# lines_master.net
KiCad netlist of a schematic drawn in EAGLE
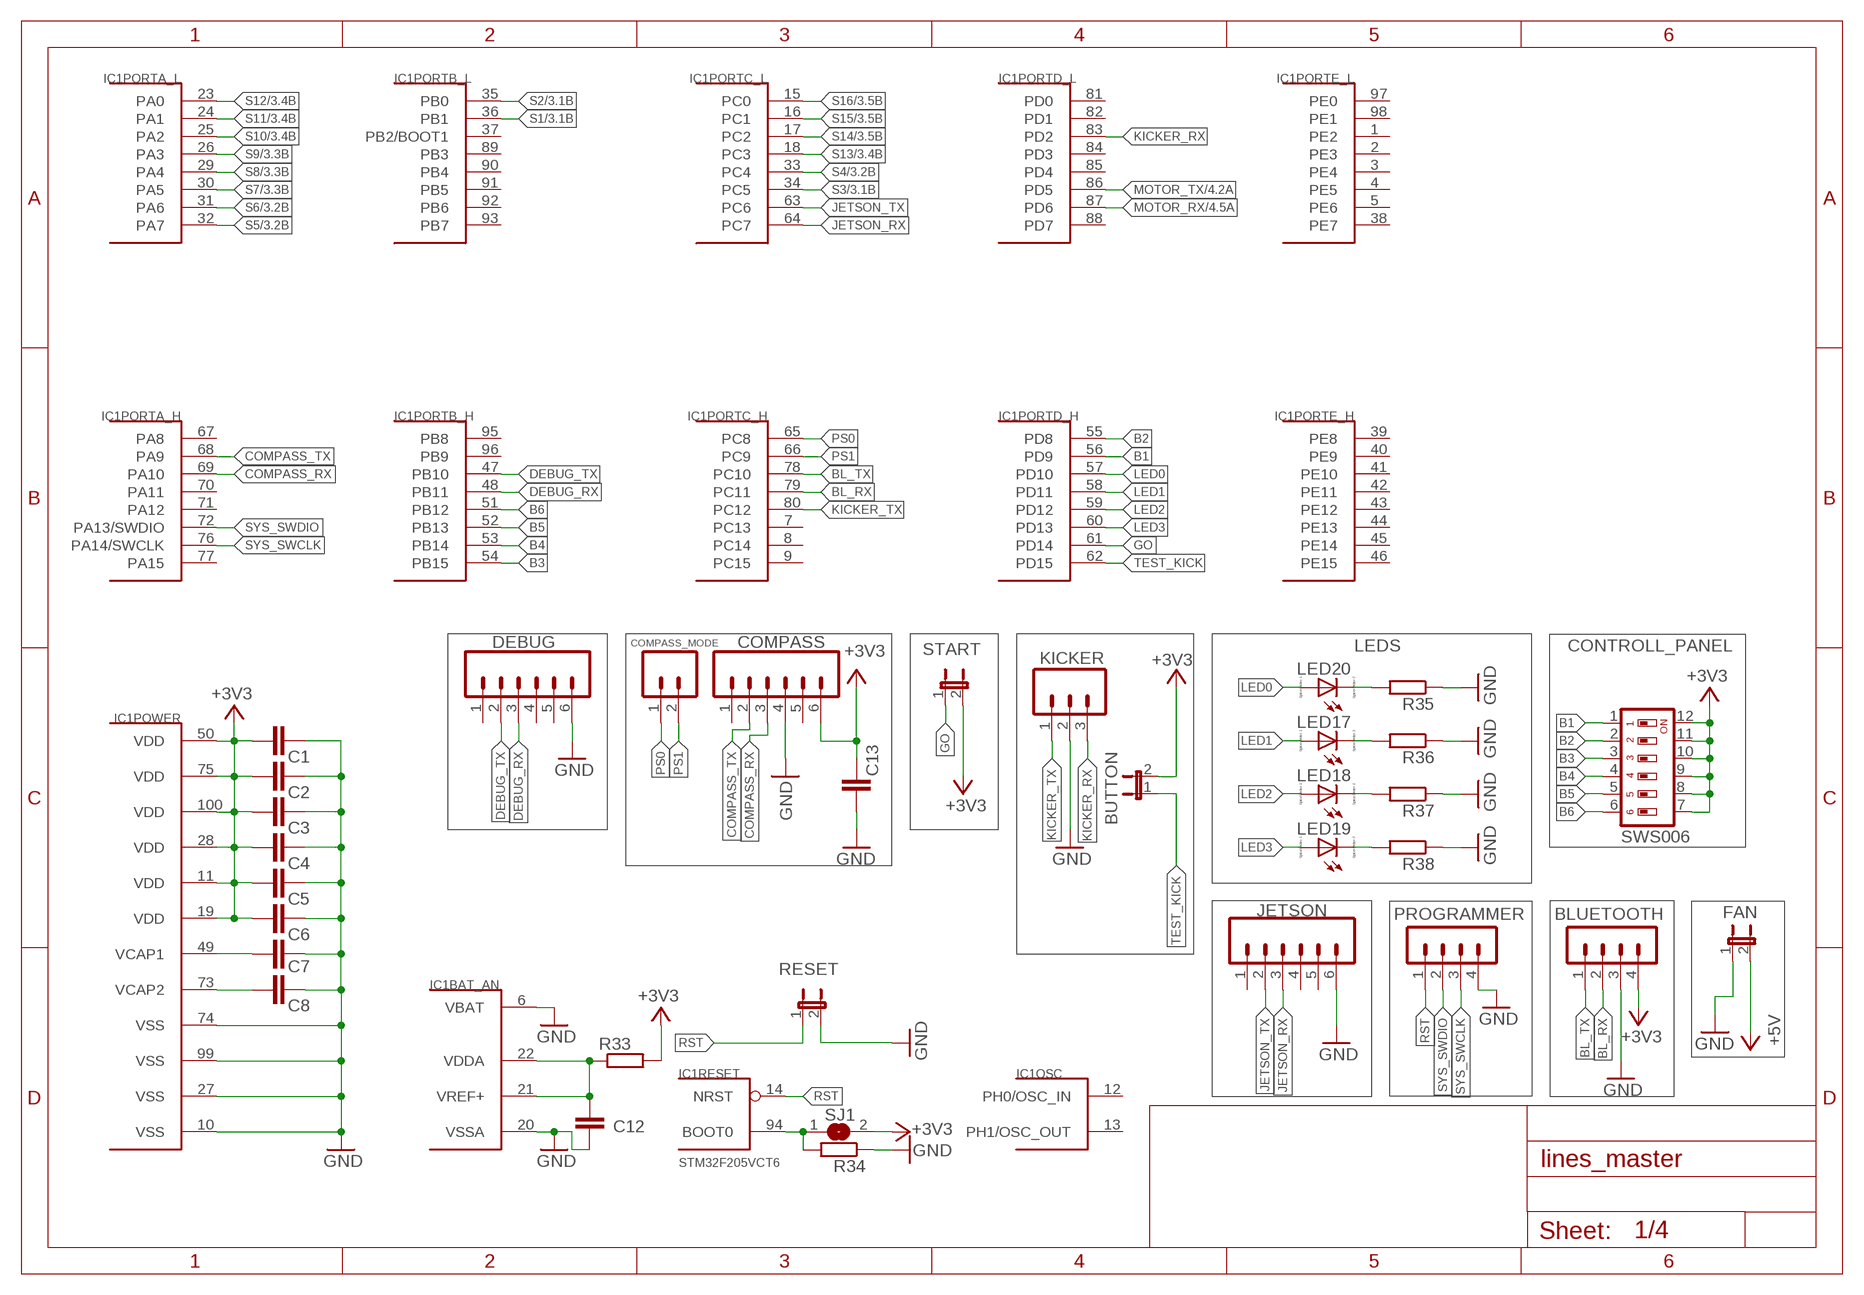
[diagram p0: schematic, sheet 1]
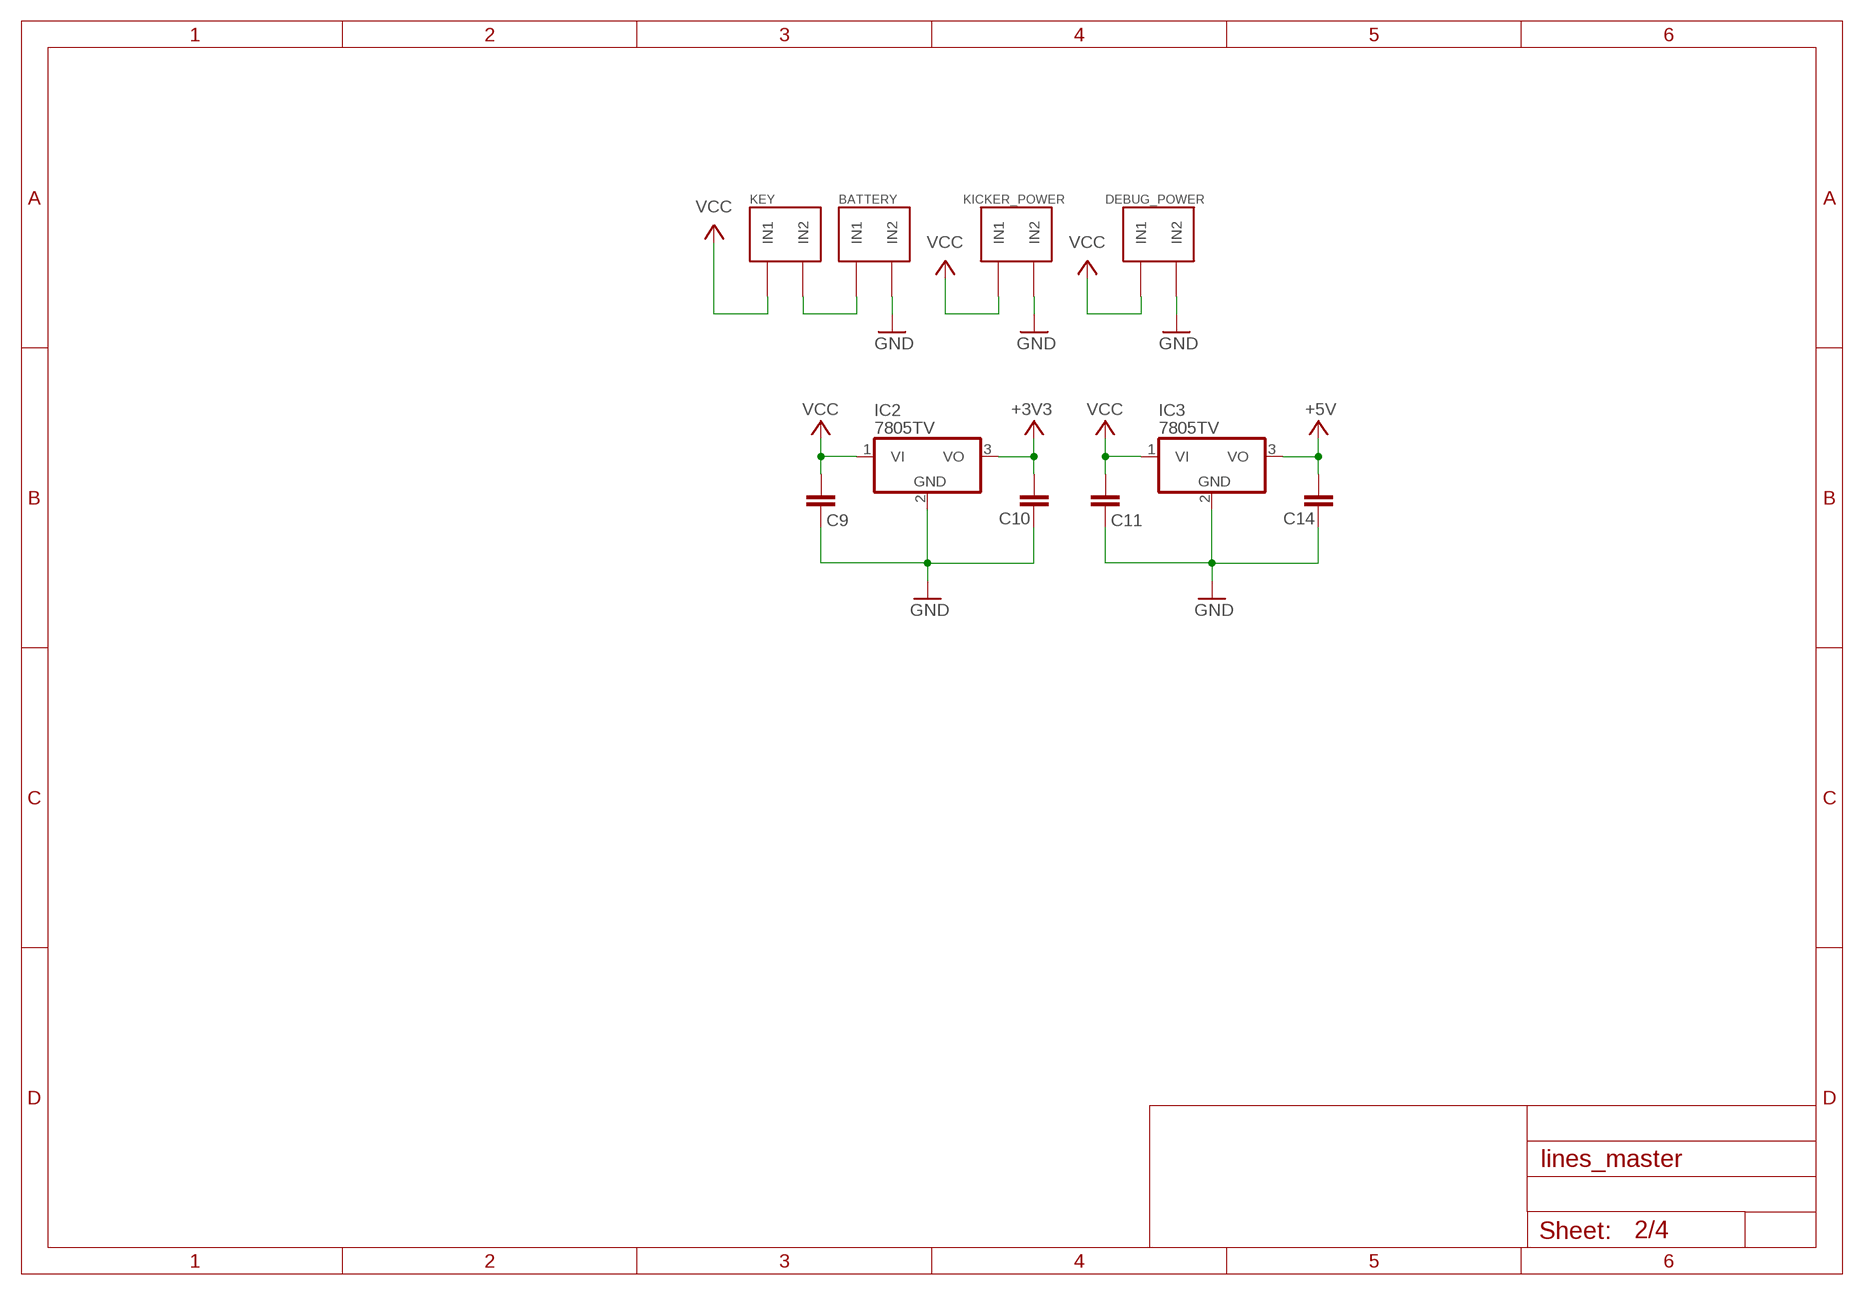
[diagram p1: schematic, sheet 2]
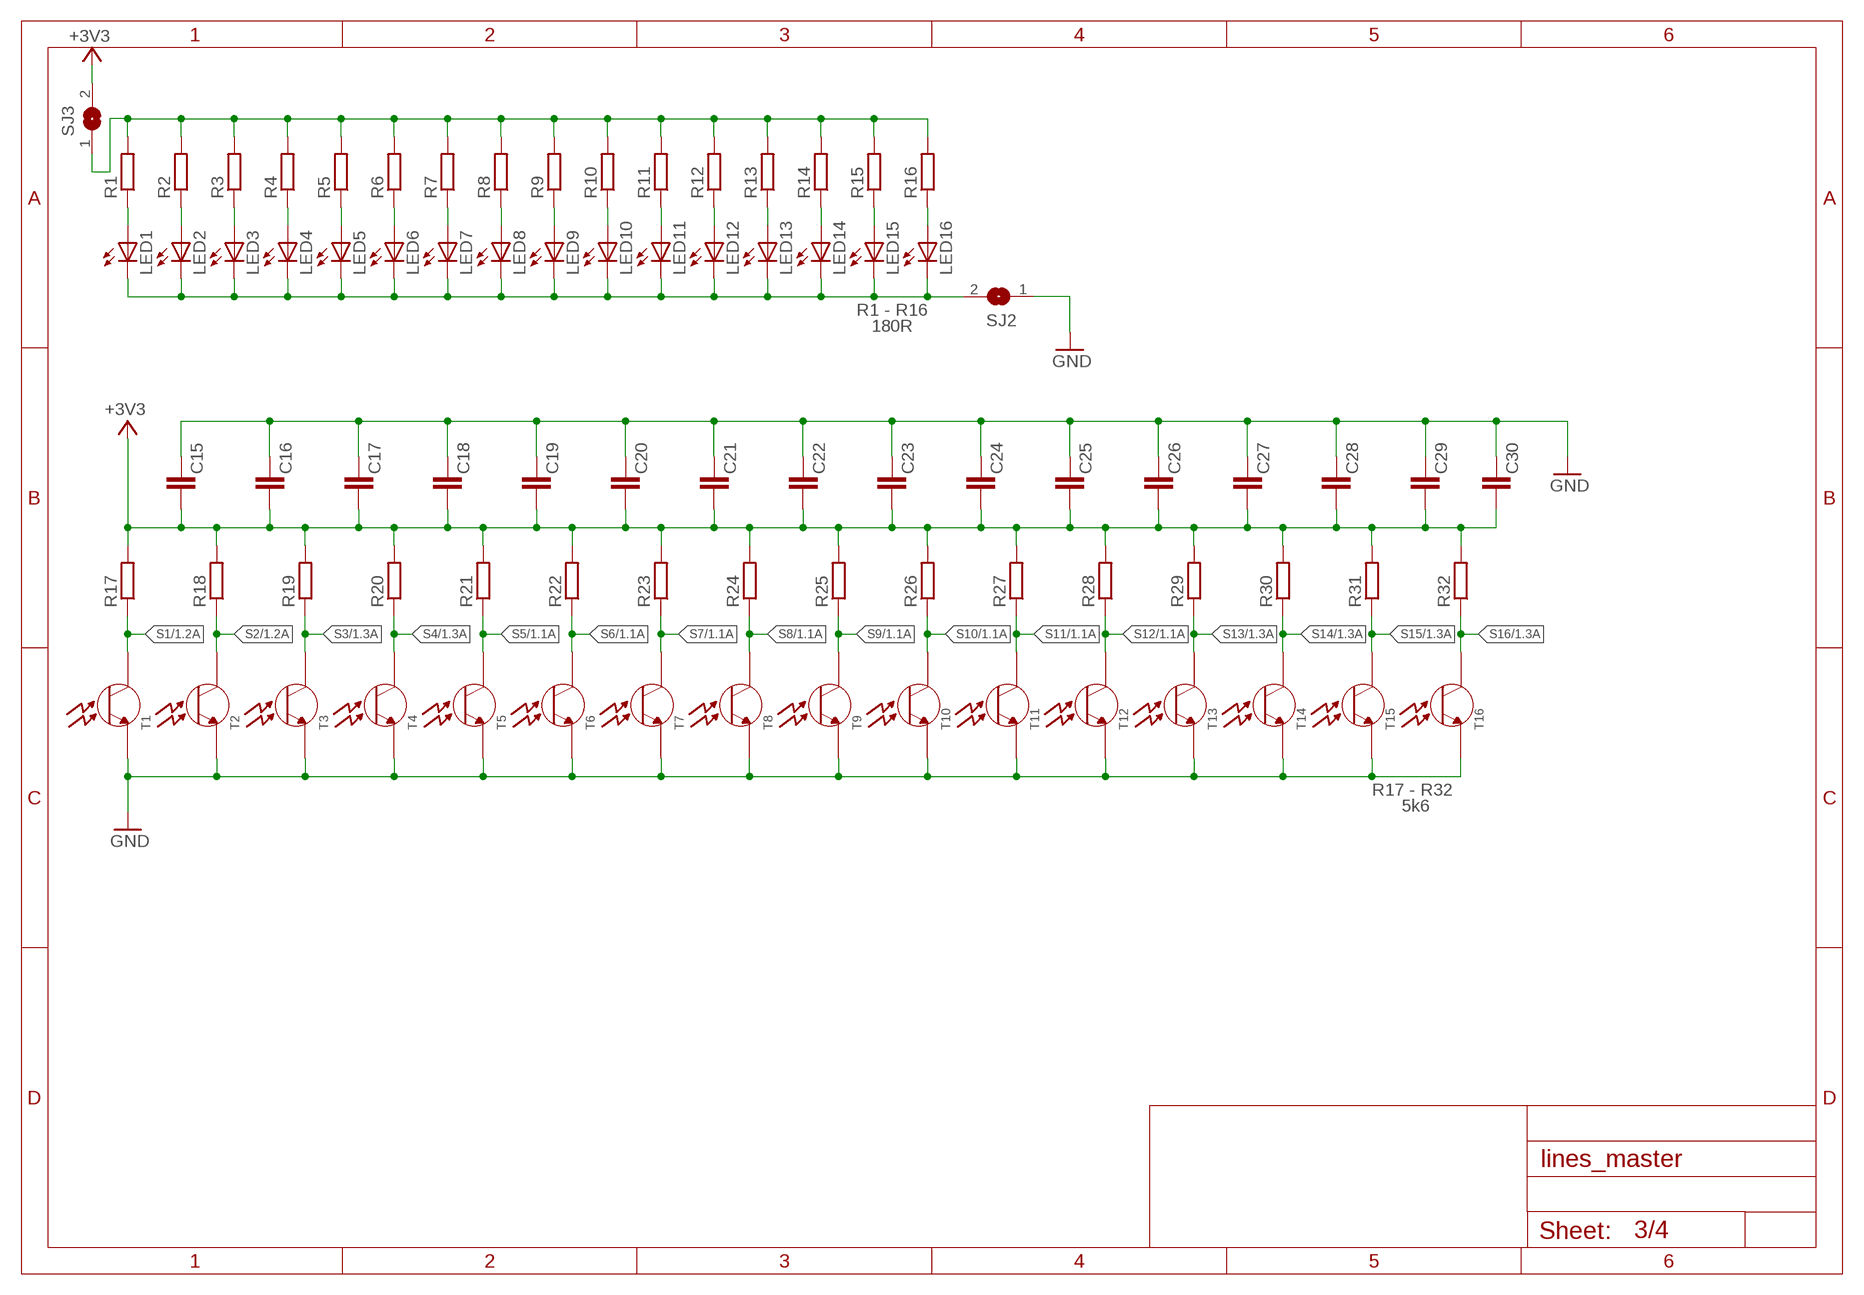
[diagram p2: schematic, sheet 3]
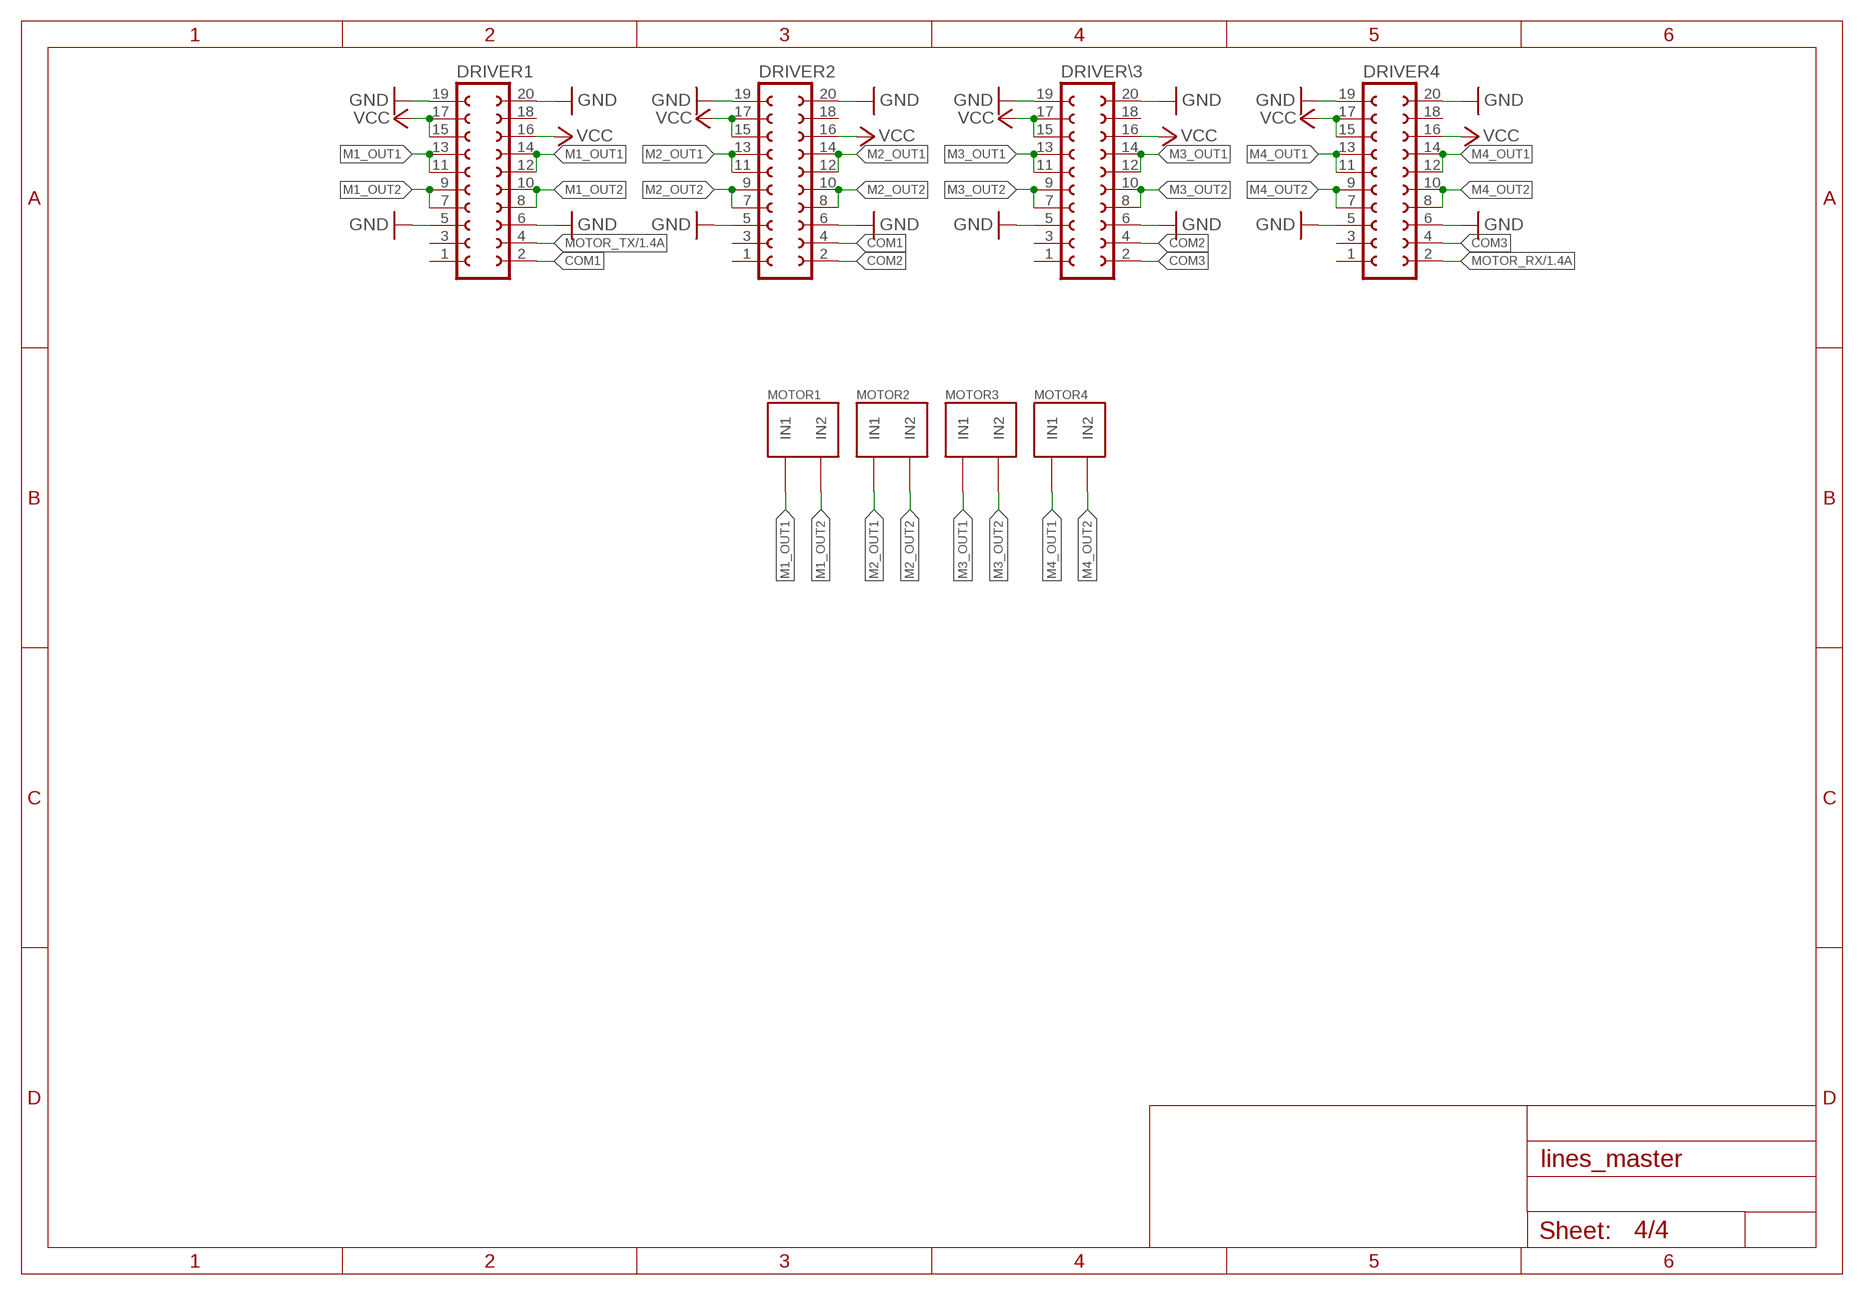
[diagram p3: schematic, sheet 4]

(export (version "E")
  (design (tool "Eeschema 10.0.6"))
  (components
    (comp (ref "DRIVER1")
      (value "FE10-2")
      (footprint "eagle-import:FE10-2")
      (libsource (lib "eagle-import") (part "FE10-2"))
    )
    (comp (ref "DRIVER2")
      (value "FE10-2")
      (footprint "eagle-import:FE10-2")
      (libsource (lib "eagle-import") (part "FE10-2"))
    )
    (comp (ref "DRIVER4")
      (value "FE10-2")
      (footprint "eagle-import:FE10-2")
      (libsource (lib "eagle-import") (part "FE10-2"))
    )
    (comp (ref "DRIVER\\3")
      (value "FE10-2")
      (footprint "eagle-import:FE10-2")
      (libsource (lib "eagle-import") (part "FE10-2"))
    )
    (comp (ref "MOTOR1")
      (value "MOTOR_CONNECTOR")
      (footprint "eagle-import:MOTOR_CONNECTOR")
      (libsource (lib "eagle-import") (part "MOTOR_CONNECTOR"))
    )
    (comp (ref "MOTOR2")
      (value "MOTOR_CONNECTOR")
      (footprint "eagle-import:MOTOR_CONNECTOR")
      (libsource (lib "eagle-import") (part "MOTOR_CONNECTOR"))
    )
    (comp (ref "MOTOR3")
      (value "MOTOR_CONNECTOR")
      (footprint "eagle-import:MOTOR_CONNECTOR")
      (libsource (lib "eagle-import") (part "MOTOR_CONNECTOR"))
    )
    (comp (ref "MOTOR4")
      (value "MOTOR_CONNECTOR")
      (footprint "eagle-import:MOTOR_CONNECTOR")
      (libsource (lib "eagle-import") (part "MOTOR_CONNECTOR"))
    )
    (comp (ref "BLUETOOTH")
      (value "MA04-1")
      (footprint "eagle-import:MA04-1")
      (libsource (lib "eagle-import") (part "MA04-1"))
    )
    (comp (ref "BUTTON")
      (value "JP1E")
      (footprint "eagle-import:JP1")
      (libsource (lib "eagle-import") (part "JP1E"))
    )
    (comp (ref "C1")
      (value "100K")
      (footprint "eagle-import:C0603")
      (libsource (lib "eagle-import") (part "C-EUC0603"))
    )
    (comp (ref "C2")
      (value "100K")
      (footprint "eagle-import:C0603")
      (libsource (lib "eagle-import") (part "C-EUC0603"))
    )
    (comp (ref "C3")
      (value "100K")
      (footprint "eagle-import:C0603")
      (libsource (lib "eagle-import") (part "C-EUC0603"))
    )
    (comp (ref "C4")
      (value "100K")
      (footprint "eagle-import:C0603")
      (libsource (lib "eagle-import") (part "C-EUC0603"))
    )
    (comp (ref "C5")
      (value "100K")
      (footprint "eagle-import:C0603")
      (libsource (lib "eagle-import") (part "C-EUC0603"))
    )
    (comp (ref "C6")
      (value "100K")
      (footprint "eagle-import:C0603")
      (libsource (lib "eagle-import") (part "C-EUC0603"))
    )
    (comp (ref "C7")
      (value "2M2")
      (footprint "eagle-import:C0805")
      (libsource (lib "eagle-import") (part "C-EUC0805"))
    )
    (comp (ref "C8")
      (value "2M2")
      (footprint "eagle-import:C0805")
      (libsource (lib "eagle-import") (part "C-EUC0805"))
    )
    (comp (ref "C12")
      (value "100K")
      (footprint "eagle-import:C0603")
      (libsource (lib "eagle-import") (part "C-EUC0603"))
    )
    (comp (ref "C13")
      (value "100K")
      (footprint "eagle-import:C0603")
      (libsource (lib "eagle-import") (part "C-EUC0603"))
    )
    (comp (ref "COMPASS")
      (value "M06")
      (footprint "eagle-import:06P")
      (libsource (lib "eagle-import") (part "M06"))
    )
    (comp (ref "COMPASS_MODE")
      (value "M02")
      (footprint "eagle-import:02P")
      (libsource (lib "eagle-import") (part "M02"))
    )
    (comp (ref "CONTROLL_PANEL")
      (value "SWS006")
      (footprint "eagle-import:SMS-006")
      (libsource (lib "eagle-import") (part "SWS006"))
    )
    (comp (ref "DEBUG")
      (value "M06")
      (footprint "eagle-import:06P")
      (libsource (lib "eagle-import") (part "M06"))
    )
    (comp (ref "FAN")
      (value "JP1E")
      (footprint "eagle-import:JP1")
      (libsource (lib "eagle-import") (part "JP1E"))
    )
    (comp (ref "IC1")
      (value "STM32F205VCT6")
      (footprint "eagle-import:TQFP100")
      (libsource (lib "eagle-import") (part "STM32F205VCT6"))
    )
    (comp (ref "JETSON")
      (value "M06")
      (footprint "eagle-import:06P")
      (libsource (lib "eagle-import") (part "M06"))
    )
    (comp (ref "KICKER")
      (value "M03")
      (footprint "eagle-import:03P")
      (libsource (lib "eagle-import") (part "M03"))
    )
    (comp (ref "LED17")
      (value "LED_E")
      (footprint "eagle-import:LED_1206")
      (libsource (lib "eagle-import") (part "LED_E"))
    )
    (comp (ref "LED18")
      (value "LED_E")
      (footprint "eagle-import:LED_1206")
      (libsource (lib "eagle-import") (part "LED_E"))
    )
    (comp (ref "LED19")
      (value "LED_E")
      (footprint "eagle-import:LED_1206")
      (libsource (lib "eagle-import") (part "LED_E"))
    )
    (comp (ref "LED20")
      (value "LED_E")
      (footprint "eagle-import:LED_1206")
      (libsource (lib "eagle-import") (part "LED_E"))
    )
    (comp (ref "PROGRAMMER")
      (value "MA04-1")
      (footprint "eagle-import:MA04-1")
      (libsource (lib "eagle-import") (part "MA04-1"))
    )
    (comp (ref "R33")
      (value "R-EU_R1206")
      (footprint "eagle-import:R1206")
      (libsource (lib "eagle-import") (part "R-EU_R1206"))
    )
    (comp (ref "R34")
      (value "R-EU_R0603")
      (footprint "eagle-import:R0603")
      (libsource (lib "eagle-import") (part "R-EU_R0603"))
    )
    (comp (ref "R35")
      (value "R-EU_R0603")
      (footprint "eagle-import:R0603")
      (libsource (lib "eagle-import") (part "R-EU_R0603"))
    )
    (comp (ref "R36")
      (value "R-EU_R0603")
      (footprint "eagle-import:R0603")
      (libsource (lib "eagle-import") (part "R-EU_R0603"))
    )
    (comp (ref "R37")
      (value "R-EU_R0603")
      (footprint "eagle-import:R0603")
      (libsource (lib "eagle-import") (part "R-EU_R0603"))
    )
    (comp (ref "R38")
      (value "R-EU_R0603")
      (footprint "eagle-import:R0603")
      (libsource (lib "eagle-import") (part "R-EU_R0603"))
    )
    (comp (ref "RESET")
      (value "JP1E")
      (footprint "eagle-import:JP1")
      (libsource (lib "eagle-import") (part "JP1E"))
    )
    (comp (ref "SJ1") (value "SJ") (footprint "eagle-import:SJ") (libsource (lib "eagle-import") (part "SJ")))
    (comp (ref "START")
      (value "JP1E")
      (footprint "eagle-import:JP1")
      (libsource (lib "eagle-import") (part "JP1E"))
    )
    (comp (ref "BATTERY")
      (value "MOTOR_CONNECTOR")
      (footprint "eagle-import:MOTOR_CONNECTOR")
      (libsource (lib "eagle-import") (part "MOTOR_CONNECTOR"))
    )
    (comp (ref "C9")
      (value "100K")
      (footprint "eagle-import:C0603")
      (libsource (lib "eagle-import") (part "C-EUC0603"))
    )
    (comp (ref "C10")
      (value "100K")
      (footprint "eagle-import:C0603")
      (libsource (lib "eagle-import") (part "C-EUC0603"))
    )
    (comp (ref "C11")
      (value "100K")
      (footprint "eagle-import:C0603")
      (libsource (lib "eagle-import") (part "C-EUC0603"))
    )
    (comp (ref "C14")
      (value "100K")
      (footprint "eagle-import:C0603")
      (libsource (lib "eagle-import") (part "C-EUC0603"))
    )
    (comp (ref "DEBUG_POWER")
      (value "MOTOR_CONNECTOR")
      (footprint "eagle-import:MOTOR_CONNECTOR")
      (libsource (lib "eagle-import") (part "MOTOR_CONNECTOR"))
    )
    (comp (ref "IC2")
      (value "7805TV")
      (footprint "eagle-import:TO220V")
      (libsource (lib "eagle-import") (part "78TV05"))
    )
    (comp (ref "IC3")
      (value "7805TV")
      (footprint "eagle-import:TO220V")
      (libsource (lib "eagle-import") (part "78TV05"))
    )
    (comp (ref "KEY")
      (value "MOTOR_CONNECTOR")
      (footprint "eagle-import:MOTOR_CONNECTOR")
      (libsource (lib "eagle-import") (part "MOTOR_CONNECTOR"))
    )
    (comp (ref "KICKER_POWER")
      (value "MOTOR_CONNECTOR")
      (footprint "eagle-import:MOTOR_CONNECTOR")
      (libsource (lib "eagle-import") (part "MOTOR_CONNECTOR"))
    )
    (comp (ref "C15")
      (value "100K")
      (footprint "eagle-import:C0603")
      (libsource (lib "eagle-import") (part "C-EUC0603"))
    )
    (comp (ref "C16")
      (value "100K")
      (footprint "eagle-import:C0603")
      (libsource (lib "eagle-import") (part "C-EUC0603"))
    )
    (comp (ref "C17")
      (value "100K")
      (footprint "eagle-import:C0603")
      (libsource (lib "eagle-import") (part "C-EUC0603"))
    )
    (comp (ref "C18")
      (value "100K")
      (footprint "eagle-import:C0603")
      (libsource (lib "eagle-import") (part "C-EUC0603"))
    )
    (comp (ref "C19")
      (value "100K")
      (footprint "eagle-import:C0603")
      (libsource (lib "eagle-import") (part "C-EUC0603"))
    )
    (comp (ref "C20")
      (value "100K")
      (footprint "eagle-import:C0603")
      (libsource (lib "eagle-import") (part "C-EUC0603"))
    )
    (comp (ref "C21")
      (value "100K")
      (footprint "eagle-import:C0603")
      (libsource (lib "eagle-import") (part "C-EUC0603"))
    )
    (comp (ref "C22")
      (value "100K")
      (footprint "eagle-import:C0603")
      (libsource (lib "eagle-import") (part "C-EUC0603"))
    )
    (comp (ref "C23")
      (value "100K")
      (footprint "eagle-import:C0603")
      (libsource (lib "eagle-import") (part "C-EUC0603"))
    )
    (comp (ref "C24")
      (value "100K")
      (footprint "eagle-import:C0603")
      (libsource (lib "eagle-import") (part "C-EUC0603"))
    )
    (comp (ref "C25")
      (value "100K")
      (footprint "eagle-import:C0603")
      (libsource (lib "eagle-import") (part "C-EUC0603"))
    )
    (comp (ref "C26")
      (value "100K")
      (footprint "eagle-import:C0603")
      (libsource (lib "eagle-import") (part "C-EUC0603"))
    )
    (comp (ref "C27")
      (value "100K")
      (footprint "eagle-import:C0603")
      (libsource (lib "eagle-import") (part "C-EUC0603"))
    )
    (comp (ref "C28")
      (value "100K")
      (footprint "eagle-import:C0603")
      (libsource (lib "eagle-import") (part "C-EUC0603"))
    )
    (comp (ref "C29")
      (value "100K")
      (footprint "eagle-import:C0603")
      (libsource (lib "eagle-import") (part "C-EUC0603"))
    )
    (comp (ref "C30")
      (value "100K")
      (footprint "eagle-import:C0603")
      (libsource (lib "eagle-import") (part "C-EUC0603"))
    )
    (comp (ref "LED1")
      (value "LEDKA-3528ASYC")
      (footprint "eagle-import:KA-3528ASYC")
      (libsource (lib "eagle-import") (part "LEDKA-3528ASYC"))
    )
    (comp (ref "LED2")
      (value "LEDKA-3528ASYC")
      (footprint "eagle-import:KA-3528ASYC")
      (libsource (lib "eagle-import") (part "LEDKA-3528ASYC"))
    )
    (comp (ref "LED3")
      (value "LEDKA-3528ASYC")
      (footprint "eagle-import:KA-3528ASYC")
      (libsource (lib "eagle-import") (part "LEDKA-3528ASYC"))
    )
    (comp (ref "LED4")
      (value "LEDKA-3528ASYC")
      (footprint "eagle-import:KA-3528ASYC")
      (libsource (lib "eagle-import") (part "LEDKA-3528ASYC"))
    )
    (comp (ref "LED5")
      (value "LEDKA-3528ASYC")
      (footprint "eagle-import:KA-3528ASYC")
      (libsource (lib "eagle-import") (part "LEDKA-3528ASYC"))
    )
    (comp (ref "LED6")
      (value "LEDKA-3528ASYC")
      (footprint "eagle-import:KA-3528ASYC")
      (libsource (lib "eagle-import") (part "LEDKA-3528ASYC"))
    )
    (comp (ref "LED7")
      (value "LEDKA-3528ASYC")
      (footprint "eagle-import:KA-3528ASYC")
      (libsource (lib "eagle-import") (part "LEDKA-3528ASYC"))
    )
    (comp (ref "LED8")
      (value "LEDKA-3528ASYC")
      (footprint "eagle-import:KA-3528ASYC")
      (libsource (lib "eagle-import") (part "LEDKA-3528ASYC"))
    )
    (comp (ref "LED9")
      (value "LEDKA-3528ASYC")
      (footprint "eagle-import:KA-3528ASYC")
      (libsource (lib "eagle-import") (part "LEDKA-3528ASYC"))
    )
    (comp (ref "LED10")
      (value "LEDKA-3528ASYC")
      (footprint "eagle-import:KA-3528ASYC")
      (libsource (lib "eagle-import") (part "LEDKA-3528ASYC"))
    )
    (comp (ref "LED11")
      (value "LEDKA-3528ASYC")
      (footprint "eagle-import:KA-3528ASYC")
      (libsource (lib "eagle-import") (part "LEDKA-3528ASYC"))
    )
    (comp (ref "LED12")
      (value "LEDKA-3528ASYC")
      (footprint "eagle-import:KA-3528ASYC")
      (libsource (lib "eagle-import") (part "LEDKA-3528ASYC"))
    )
    (comp (ref "LED13")
      (value "LEDKA-3528ASYC")
      (footprint "eagle-import:KA-3528ASYC")
      (libsource (lib "eagle-import") (part "LEDKA-3528ASYC"))
    )
    (comp (ref "LED14")
      (value "LEDKA-3528ASYC")
      (footprint "eagle-import:KA-3528ASYC")
      (libsource (lib "eagle-import") (part "LEDKA-3528ASYC"))
    )
    (comp (ref "LED15")
      (value "LEDKA-3528ASYC")
      (footprint "eagle-import:KA-3528ASYC")
      (libsource (lib "eagle-import") (part "LEDKA-3528ASYC"))
    )
    (comp (ref "LED16")
      (value "LEDKA-3528ASYC")
      (footprint "eagle-import:KA-3528ASYC")
      (libsource (lib "eagle-import") (part "LEDKA-3528ASYC"))
    )
    (comp (ref "R1")
      (value "180R")
      (footprint "eagle-import:R0603")
      (libsource (lib "eagle-import") (part "R-EU_R0603"))
    )
    (comp (ref "R2")
      (value "180R")
      (footprint "eagle-import:R0603")
      (libsource (lib "eagle-import") (part "R-EU_R0603"))
    )
    (comp (ref "R3")
      (value "180R")
      (footprint "eagle-import:R0603")
      (libsource (lib "eagle-import") (part "R-EU_R0603"))
    )
    (comp (ref "R4")
      (value "180R")
      (footprint "eagle-import:R0603")
      (libsource (lib "eagle-import") (part "R-EU_R0603"))
    )
    (comp (ref "R5")
      (value "180R")
      (footprint "eagle-import:R0603")
      (libsource (lib "eagle-import") (part "R-EU_R0603"))
    )
    (comp (ref "R6")
      (value "180R")
      (footprint "eagle-import:R0603")
      (libsource (lib "eagle-import") (part "R-EU_R0603"))
    )
    (comp (ref "R7")
      (value "180R")
      (footprint "eagle-import:R0603")
      (libsource (lib "eagle-import") (part "R-EU_R0603"))
    )
    (comp (ref "R8")
      (value "180R")
      (footprint "eagle-import:R0603")
      (libsource (lib "eagle-import") (part "R-EU_R0603"))
    )
    (comp (ref "R9")
      (value "180R")
      (footprint "eagle-import:R0603")
      (libsource (lib "eagle-import") (part "R-EU_R0603"))
    )
    (comp (ref "R10")
      (value "180R")
      (footprint "eagle-import:R0603")
      (libsource (lib "eagle-import") (part "R-EU_R0603"))
    )
    (comp (ref "R11")
      (value "180R")
      (footprint "eagle-import:R0603")
      (libsource (lib "eagle-import") (part "R-EU_R0603"))
    )
    (comp (ref "R12")
      (value "180R")
      (footprint "eagle-import:R0603")
      (libsource (lib "eagle-import") (part "R-EU_R0603"))
    )
    (comp (ref "R13")
      (value "180R")
      (footprint "eagle-import:R0603")
      (libsource (lib "eagle-import") (part "R-EU_R0603"))
    )
    (comp (ref "R14")
      (value "180R")
      (footprint "eagle-import:R0603")
      (libsource (lib "eagle-import") (part "R-EU_R0603"))
    )
    (comp (ref "R15")
      (value "180R")
      (footprint "eagle-import:R0603")
      (libsource (lib "eagle-import") (part "R-EU_R0603"))
    )
    (comp (ref "R16")
      (value "180R")
      (footprint "eagle-import:R0603")
      (libsource (lib "eagle-import") (part "R-EU_R0603"))
    )
    (comp (ref "R17")
      (value "5K6")
      (footprint "eagle-import:R0603")
      (libsource (lib "eagle-import") (part "R-EU_R0603"))
    )
    (comp (ref "R18")
      (value "5K6")
      (footprint "eagle-import:R0603")
      (libsource (lib "eagle-import") (part "R-EU_R0603"))
    )
    (comp (ref "R19")
      (value "5K6")
      (footprint "eagle-import:R0603")
      (libsource (lib "eagle-import") (part "R-EU_R0603"))
    )
    (comp (ref "R20")
      (value "5K6")
      (footprint "eagle-import:R0603")
      (libsource (lib "eagle-import") (part "R-EU_R0603"))
    )
    (comp (ref "R21")
      (value "5K6")
      (footprint "eagle-import:R0603")
      (libsource (lib "eagle-import") (part "R-EU_R0603"))
    )
    (comp (ref "R22")
      (value "5K6")
      (footprint "eagle-import:R0603")
      (libsource (lib "eagle-import") (part "R-EU_R0603"))
    )
    (comp (ref "R23")
      (value "5K6")
      (footprint "eagle-import:R0603")
      (libsource (lib "eagle-import") (part "R-EU_R0603"))
    )
    (comp (ref "R24")
      (value "5K6")
      (footprint "eagle-import:R0603")
      (libsource (lib "eagle-import") (part "R-EU_R0603"))
    )
    (comp (ref "R25")
      (value "5K6")
      (footprint "eagle-import:R0603")
      (libsource (lib "eagle-import") (part "R-EU_R0603"))
    )
    (comp (ref "R26")
      (value "5K6")
      (footprint "eagle-import:R0603")
      (libsource (lib "eagle-import") (part "R-EU_R0603"))
    )
    (comp (ref "R27")
      (value "5K6")
      (footprint "eagle-import:R0603")
      (libsource (lib "eagle-import") (part "R-EU_R0603"))
    )
    (comp (ref "R28")
      (value "5K6")
      (footprint "eagle-import:R0603")
      (libsource (lib "eagle-import") (part "R-EU_R0603"))
    )
    (comp (ref "R29")
      (value "5K6")
      (footprint "eagle-import:R0603")
      (libsource (lib "eagle-import") (part "R-EU_R0603"))
    )
    (comp (ref "R30")
      (value "5K6")
      (footprint "eagle-import:R0603")
      (libsource (lib "eagle-import") (part "R-EU_R0603"))
    )
    (comp (ref "R31")
      (value "5K6")
      (footprint "eagle-import:R0603")
      (libsource (lib "eagle-import") (part "R-EU_R0603"))
    )
    (comp (ref "R32")
      (value "5K6")
      (footprint "eagle-import:R0603")
      (libsource (lib "eagle-import") (part "R-EU_R0603"))
    )
    (comp (ref "SJ2") (value "SJ") (footprint "eagle-import:SJ") (libsource (lib "eagle-import") (part "SJ")))
    (comp (ref "SJ3") (value "SJ") (footprint "eagle-import:SJ") (libsource (lib "eagle-import") (part "SJ")))
    (comp (ref "T1")
      (value "LL-S150-1A")
      (footprint "eagle-import:LL-S150PTC-1A")
      (libsource (lib "eagle-import") (part "LL-S150-1A"))
    )
    (comp (ref "T2")
      (value "LL-S150-1A")
      (footprint "eagle-import:LL-S150PTC-1A")
      (libsource (lib "eagle-import") (part "LL-S150-1A"))
    )
    (comp (ref "T3")
      (value "LL-S150-1A")
      (footprint "eagle-import:LL-S150PTC-1A")
      (libsource (lib "eagle-import") (part "LL-S150-1A"))
    )
    (comp (ref "T4")
      (value "LL-S150-1A")
      (footprint "eagle-import:LL-S150PTC-1A")
      (libsource (lib "eagle-import") (part "LL-S150-1A"))
    )
    (comp (ref "T5")
      (value "LL-S150-1A")
      (footprint "eagle-import:LL-S150PTC-1A")
      (libsource (lib "eagle-import") (part "LL-S150-1A"))
    )
    (comp (ref "T6")
      (value "LL-S150-1A")
      (footprint "eagle-import:LL-S150PTC-1A")
      (libsource (lib "eagle-import") (part "LL-S150-1A"))
    )
    (comp (ref "T7")
      (value "LL-S150-1A")
      (footprint "eagle-import:LL-S150PTC-1A")
      (libsource (lib "eagle-import") (part "LL-S150-1A"))
    )
    (comp (ref "T8")
      (value "LL-S150-1A")
      (footprint "eagle-import:LL-S150PTC-1A")
      (libsource (lib "eagle-import") (part "LL-S150-1A"))
    )
    (comp (ref "T9")
      (value "LL-S150-1A")
      (footprint "eagle-import:LL-S150PTC-1A")
      (libsource (lib "eagle-import") (part "LL-S150-1A"))
    )
    (comp (ref "T10")
      (value "LL-S150-1A")
      (footprint "eagle-import:LL-S150PTC-1A")
      (libsource (lib "eagle-import") (part "LL-S150-1A"))
    )
    (comp (ref "T11")
      (value "LL-S150-1A")
      (footprint "eagle-import:LL-S150PTC-1A")
      (libsource (lib "eagle-import") (part "LL-S150-1A"))
    )
    (comp (ref "T12")
      (value "LL-S150-1A")
      (footprint "eagle-import:LL-S150PTC-1A")
      (libsource (lib "eagle-import") (part "LL-S150-1A"))
    )
    (comp (ref "T13")
      (value "LL-S150-1A")
      (footprint "eagle-import:LL-S150PTC-1A")
      (libsource (lib "eagle-import") (part "LL-S150-1A"))
    )
    (comp (ref "T14")
      (value "LL-S150-1A")
      (footprint "eagle-import:LL-S150PTC-1A")
      (libsource (lib "eagle-import") (part "LL-S150-1A"))
    )
    (comp (ref "T15")
      (value "LL-S150-1A")
      (footprint "eagle-import:LL-S150PTC-1A")
      (libsource (lib "eagle-import") (part "LL-S150-1A"))
    )
    (comp (ref "T16")
      (value "LL-S150-1A")
      (footprint "eagle-import:LL-S150PTC-1A")
      (libsource (lib "eagle-import") (part "LL-S150-1A"))
    )
  )
  (nets
    (net (code "1") (name "+3V3") (class "Default")
      (node (ref "BLUETOOTH") (pin "4") (pinfunction "4_4") (pintype "passive"))
      (node (ref "BUTTON") (pin "2") (pinfunction "2_2") (pintype "passive"))
      (node (ref "C1") (pin "2") (pinfunction "2_2") (pintype "passive"))
      (node (ref "C10") (pin "2") (pinfunction "2_2") (pintype "passive"))
      (node (ref "C13") (pin "1") (pinfunction "1_1") (pintype "passive"))
      (node (ref "C15") (pin "2") (pinfunction "2_2") (pintype "passive"))
      (node (ref "C16") (pin "2") (pinfunction "2_2") (pintype "passive"))
      (node (ref "C17") (pin "2") (pinfunction "2_2") (pintype "passive"))
      (node (ref "C18") (pin "2") (pinfunction "2_2") (pintype "passive"))
      (node (ref "C19") (pin "2") (pinfunction "2_2") (pintype "passive"))
      (node (ref "C2") (pin "2") (pinfunction "2_2") (pintype "passive"))
      (node (ref "C20") (pin "2") (pinfunction "2_2") (pintype "passive"))
      (node (ref "C21") (pin "2") (pinfunction "2_2") (pintype "passive"))
      (node (ref "C22") (pin "2") (pinfunction "2_2") (pintype "passive"))
      (node (ref "C23") (pin "2") (pinfunction "2_2") (pintype "passive"))
      (node (ref "C24") (pin "2") (pinfunction "2_2") (pintype "passive"))
      (node (ref "C25") (pin "2") (pinfunction "2_2") (pintype "passive"))
      (node (ref "C26") (pin "2") (pinfunction "2_2") (pintype "passive"))
      (node (ref "C27") (pin "2") (pinfunction "2_2") (pintype "passive"))
      (node (ref "C28") (pin "2") (pinfunction "2_2") (pintype "passive"))
      (node (ref "C29") (pin "2") (pinfunction "2_2") (pintype "passive"))
      (node (ref "C3") (pin "2") (pinfunction "2_2") (pintype "passive"))
      (node (ref "C30") (pin "2") (pinfunction "2_2") (pintype "passive"))
      (node (ref "C4") (pin "2") (pinfunction "2_2") (pintype "passive"))
      (node (ref "C5") (pin "2") (pinfunction "2_2") (pintype "passive"))
      (node (ref "C6") (pin "2") (pinfunction "2_2") (pintype "passive"))
      (node (ref "COMPASS") (pin "6") (pinfunction "6_6") (pintype "passive"))
      (node (ref "CONTROLL_PANEL") (pin "10") (pinfunction "10_10") (pintype "passive"))
      (node (ref "CONTROLL_PANEL") (pin "11") (pinfunction "11_11") (pintype "passive"))
      (node (ref "CONTROLL_PANEL") (pin "12") (pinfunction "12_12") (pintype "passive"))
      (node (ref "CONTROLL_PANEL") (pin "7") (pinfunction "7_7") (pintype "passive"))
      (node (ref "CONTROLL_PANEL") (pin "8") (pinfunction "8_8") (pintype "passive"))
      (node (ref "CONTROLL_PANEL") (pin "9") (pinfunction "9_9") (pintype "passive"))
      (node (ref "IC1") (pin "100") (pinfunction "VDD_100") (pintype "power_in"))
      (node (ref "IC1") (pin "11") (pinfunction "VDD_11") (pintype "power_in"))
      (node (ref "IC1") (pin "19") (pinfunction "VDD_19") (pintype "power_in"))
      (node (ref "IC1") (pin "28") (pinfunction "VDD_28") (pintype "power_in"))
      (node (ref "IC1") (pin "50") (pinfunction "VDD_50") (pintype "power_in"))
      (node (ref "IC1") (pin "75") (pinfunction "VDD_75") (pintype "power_in"))
      (node (ref "IC2") (pin "3") (pinfunction "VO_3") (pintype "passive"))
      (node (ref "R17") (pin "2") (pinfunction "2_2") (pintype "passive"))
      (node (ref "R18") (pin "2") (pinfunction "2_2") (pintype "passive"))
      (node (ref "R19") (pin "2") (pinfunction "2_2") (pintype "passive"))
      (node (ref "R20") (pin "2") (pinfunction "2_2") (pintype "passive"))
      (node (ref "R21") (pin "2") (pinfunction "2_2") (pintype "passive"))
      (node (ref "R22") (pin "2") (pinfunction "2_2") (pintype "passive"))
      (node (ref "R23") (pin "2") (pinfunction "2_2") (pintype "passive"))
      (node (ref "R24") (pin "2") (pinfunction "2_2") (pintype "passive"))
      (node (ref "R25") (pin "2") (pinfunction "2_2") (pintype "passive"))
      (node (ref "R26") (pin "2") (pinfunction "2_2") (pintype "passive"))
      (node (ref "R27") (pin "2") (pinfunction "2_2") (pintype "passive"))
      (node (ref "R28") (pin "2") (pinfunction "2_2") (pintype "passive"))
      (node (ref "R29") (pin "2") (pinfunction "2_2") (pintype "passive"))
      (node (ref "R30") (pin "2") (pinfunction "2_2") (pintype "passive"))
      (node (ref "R31") (pin "2") (pinfunction "2_2") (pintype "passive"))
      (node (ref "R32") (pin "2") (pinfunction "2_2") (pintype "passive"))
      (node (ref "R33") (pin "2") (pinfunction "2_2") (pintype "passive"))
      (node (ref "SJ1") (pin "2") (pinfunction "2_2") (pintype "passive"))
      (node (ref "SJ3") (pin "2") (pinfunction "2_2") (pintype "passive"))
      (node (ref "START") (pin "2") (pinfunction "2_2") (pintype "passive"))
    )
    (net (code "2") (name "+5V") (class "Default")
      (node (ref "C14") (pin "2") (pinfunction "2_2") (pintype "passive"))
      (node (ref "FAN") (pin "2") (pinfunction "2_2") (pintype "passive"))
      (node (ref "IC3") (pin "3") (pinfunction "VO_3") (pintype "passive"))
    )
    (net (code "3") (name "B1") (class "Default")
      (node (ref "CONTROLL_PANEL") (pin "1") (pinfunction "1_1") (pintype "passive"))
      (node (ref "IC1") (pin "56") (pinfunction "PD9_56") (pintype "bidirectional"))
    )
    (net (code "4") (name "B2") (class "Default")
      (node (ref "CONTROLL_PANEL") (pin "2") (pinfunction "2_2") (pintype "passive"))
      (node (ref "IC1") (pin "55") (pinfunction "PD8_55") (pintype "bidirectional"))
    )
    (net (code "5") (name "B3") (class "Default")
      (node (ref "CONTROLL_PANEL") (pin "3") (pinfunction "3_3") (pintype "passive"))
      (node (ref "IC1") (pin "54") (pinfunction "PB15_54") (pintype "bidirectional"))
    )
    (net (code "6") (name "B4") (class "Default")
      (node (ref "CONTROLL_PANEL") (pin "4") (pinfunction "4_4") (pintype "passive"))
      (node (ref "IC1") (pin "53") (pinfunction "PB14_53") (pintype "bidirectional"))
    )
    (net (code "7") (name "B5") (class "Default")
      (node (ref "CONTROLL_PANEL") (pin "5") (pinfunction "5_5") (pintype "passive"))
      (node (ref "IC1") (pin "52") (pinfunction "PB13_52") (pintype "bidirectional"))
    )
    (net (code "8") (name "B6") (class "Default")
      (node (ref "CONTROLL_PANEL") (pin "6") (pinfunction "6_6") (pintype "passive"))
      (node (ref "IC1") (pin "51") (pinfunction "PB12_51") (pintype "bidirectional"))
    )
    (net (code "9") (name "BL_RX") (class "Default")
      (node (ref "BLUETOOTH") (pin "2") (pinfunction "2_2") (pintype "passive"))
      (node (ref "IC1") (pin "79") (pinfunction "PC11_79") (pintype "bidirectional"))
    )
    (net (code "10") (name "BL_TX") (class "Default")
      (node (ref "BLUETOOTH") (pin "1") (pinfunction "1_1") (pintype "passive"))
      (node (ref "IC1") (pin "78") (pinfunction "PC10_78") (pintype "bidirectional"))
    )
    (net (code "11") (name "COM1") (class "Default")
      (node (ref "DRIVER1") (pin "2") (pinfunction "2_2") (pintype "passive"))
      (node (ref "DRIVER2") (pin "4") (pinfunction "4_4") (pintype "passive"))
    )
    (net (code "12") (name "COM2") (class "Default")
      (node (ref "DRIVER2") (pin "2") (pinfunction "2_2") (pintype "passive"))
      (node (ref "DRIVER\\3") (pin "4") (pinfunction "4_4") (pintype "passive"))
    )
    (net (code "13") (name "COM3") (class "Default")
      (node (ref "DRIVER4") (pin "4") (pinfunction "4_4") (pintype "passive"))
      (node (ref "DRIVER\\3") (pin "2") (pinfunction "2_2") (pintype "passive"))
    )
    (net (code "14") (name "COMPASS_RX") (class "Default")
      (node (ref "COMPASS") (pin "3") (pinfunction "3_3") (pintype "passive"))
      (node (ref "IC1") (pin "69") (pinfunction "PA10_69") (pintype "bidirectional"))
    )
    (net (code "15") (name "COMPASS_TX") (class "Default")
      (node (ref "COMPASS") (pin "2") (pinfunction "2_2") (pintype "passive"))
      (node (ref "IC1") (pin "68") (pinfunction "PA9_68") (pintype "bidirectional"))
    )
    (net (code "16") (name "DEBUG_RX") (class "Default")
      (node (ref "DEBUG") (pin "3") (pinfunction "3_3") (pintype "passive"))
      (node (ref "IC1") (pin "48") (pinfunction "PB11_48") (pintype "bidirectional"))
    )
    (net (code "17") (name "DEBUG_TX") (class "Default")
      (node (ref "DEBUG") (pin "2") (pinfunction "2_2") (pintype "passive"))
      (node (ref "IC1") (pin "47") (pinfunction "PB10_47") (pintype "bidirectional"))
    )
    (net (code "18") (name "GND") (class "Default")
      (node (ref "BATTERY") (pin "IN2") (pinfunction "IN2_IN2") (pintype "bidirectional"))
      (node (ref "BLUETOOTH") (pin "3") (pinfunction "3_3") (pintype "passive"))
      (node (ref "C1") (pin "1") (pinfunction "1_1") (pintype "passive"))
      (node (ref "C10") (pin "1") (pinfunction "1_1") (pintype "passive"))
      (node (ref "C11") (pin "1") (pinfunction "1_1") (pintype "passive"))
      (node (ref "C12") (pin "2") (pinfunction "2_2") (pintype "passive"))
      (node (ref "C13") (pin "2") (pinfunction "2_2") (pintype "passive"))
      (node (ref "C14") (pin "1") (pinfunction "1_1") (pintype "passive"))
      (node (ref "C15") (pin "1") (pinfunction "1_1") (pintype "passive"))
      (node (ref "C16") (pin "1") (pinfunction "1_1") (pintype "passive"))
      (node (ref "C17") (pin "1") (pinfunction "1_1") (pintype "passive"))
      (node (ref "C18") (pin "1") (pinfunction "1_1") (pintype "passive"))
      (node (ref "C19") (pin "1") (pinfunction "1_1") (pintype "passive"))
      (node (ref "C2") (pin "1") (pinfunction "1_1") (pintype "passive"))
      (node (ref "C20") (pin "1") (pinfunction "1_1") (pintype "passive"))
      (node (ref "C21") (pin "1") (pinfunction "1_1") (pintype "passive"))
      (node (ref "C22") (pin "1") (pinfunction "1_1") (pintype "passive"))
      (node (ref "C23") (pin "1") (pinfunction "1_1") (pintype "passive"))
      (node (ref "C24") (pin "1") (pinfunction "1_1") (pintype "passive"))
      (node (ref "C25") (pin "1") (pinfunction "1_1") (pintype "passive"))
      (node (ref "C26") (pin "1") (pinfunction "1_1") (pintype "passive"))
      (node (ref "C27") (pin "1") (pinfunction "1_1") (pintype "passive"))
      (node (ref "C28") (pin "1") (pinfunction "1_1") (pintype "passive"))
      (node (ref "C29") (pin "1") (pinfunction "1_1") (pintype "passive"))
      (node (ref "C3") (pin "1") (pinfunction "1_1") (pintype "passive"))
      (node (ref "C30") (pin "1") (pinfunction "1_1") (pintype "passive"))
      (node (ref "C4") (pin "1") (pinfunction "1_1") (pintype "passive"))
      (node (ref "C5") (pin "1") (pinfunction "1_1") (pintype "passive"))
      (node (ref "C6") (pin "1") (pinfunction "1_1") (pintype "passive"))
      (node (ref "C7") (pin "1") (pinfunction "1_1") (pintype "passive"))
      (node (ref "C8") (pin "1") (pinfunction "1_1") (pintype "passive"))
      (node (ref "C9") (pin "1") (pinfunction "1_1") (pintype "passive"))
      (node (ref "COMPASS") (pin "4") (pinfunction "4_4") (pintype "passive"))
      (node (ref "DEBUG") (pin "6") (pinfunction "6_6") (pintype "passive"))
      (node (ref "DEBUG_POWER") (pin "IN2") (pinfunction "IN2_IN2") (pintype "bidirectional"))
      (node (ref "DRIVER1") (pin "19") (pinfunction "19_19") (pintype "passive"))
      (node (ref "DRIVER1") (pin "20") (pinfunction "20_20") (pintype "passive"))
      (node (ref "DRIVER1") (pin "5") (pinfunction "5_5") (pintype "passive"))
      (node (ref "DRIVER1") (pin "6") (pinfunction "6_6") (pintype "passive"))
      (node (ref "DRIVER2") (pin "19") (pinfunction "19_19") (pintype "passive"))
      (node (ref "DRIVER2") (pin "20") (pinfunction "20_20") (pintype "passive"))
      (node (ref "DRIVER2") (pin "5") (pinfunction "5_5") (pintype "passive"))
      (node (ref "DRIVER2") (pin "6") (pinfunction "6_6") (pintype "passive"))
      (node (ref "DRIVER4") (pin "19") (pinfunction "19_19") (pintype "passive"))
      (node (ref "DRIVER4") (pin "20") (pinfunction "20_20") (pintype "passive"))
      (node (ref "DRIVER4") (pin "5") (pinfunction "5_5") (pintype "passive"))
      (node (ref "DRIVER4") (pin "6") (pinfunction "6_6") (pintype "passive"))
      (node (ref "DRIVER\\3") (pin "19") (pinfunction "19_19") (pintype "passive"))
      (node (ref "DRIVER\\3") (pin "20") (pinfunction "20_20") (pintype "passive"))
      (node (ref "DRIVER\\3") (pin "5") (pinfunction "5_5") (pintype "passive"))
      (node (ref "DRIVER\\3") (pin "6") (pinfunction "6_6") (pintype "passive"))
      (node (ref "FAN") (pin "1") (pinfunction "1_1") (pintype "passive"))
      (node (ref "IC1") (pin "10") (pinfunction "VSS_10") (pintype "power_in"))
      (node (ref "IC1") (pin "20") (pinfunction "VSSA_20") (pintype "power_in"))
      (node (ref "IC1") (pin "27") (pinfunction "VSS_27") (pintype "power_in"))
      (node (ref "IC1") (pin "6") (pinfunction "VBAT_6") (pintype "power_in"))
      (node (ref "IC1") (pin "74") (pinfunction "VSS_74") (pintype "power_in"))
      (node (ref "IC1") (pin "99") (pinfunction "VSS_99") (pintype "power_in"))
      (node (ref "IC2") (pin "2") (pinfunction "GND_2") (pintype "passive"))
      (node (ref "IC3") (pin "2") (pinfunction "GND_2") (pintype "passive"))
      (node (ref "JETSON") (pin "6") (pinfunction "6_6") (pintype "passive"))
      (node (ref "KICKER") (pin "2") (pinfunction "2_2") (pintype "passive"))
      (node (ref "KICKER_POWER") (pin "IN2") (pinfunction "IN2_IN2") (pintype "bidirectional"))
      (node (ref "PROGRAMMER") (pin "4") (pinfunction "4_4") (pintype "passive"))
      (node (ref "R34") (pin "1") (pinfunction "1_1") (pintype "passive"))
      (node (ref "R35") (pin "1") (pinfunction "1_1") (pintype "passive"))
      (node (ref "R36") (pin "1") (pinfunction "1_1") (pintype "passive"))
      (node (ref "R37") (pin "1") (pinfunction "1_1") (pintype "passive"))
      (node (ref "R38") (pin "1") (pinfunction "1_1") (pintype "passive"))
      (node (ref "RESET") (pin "2") (pinfunction "2_2") (pintype "passive"))
      (node (ref "SJ2") (pin "1") (pinfunction "1_1") (pintype "passive"))
      (node (ref "T1") (pin "E") (pinfunction "E_E") (pintype "bidirectional"))
      (node (ref "T10") (pin "E") (pinfunction "E_E") (pintype "bidirectional"))
      (node (ref "T11") (pin "E") (pinfunction "E_E") (pintype "bidirectional"))
      (node (ref "T12") (pin "E") (pinfunction "E_E") (pintype "bidirectional"))
      (node (ref "T13") (pin "E") (pinfunction "E_E") (pintype "bidirectional"))
      (node (ref "T14") (pin "E") (pinfunction "E_E") (pintype "bidirectional"))
      (node (ref "T15") (pin "E") (pinfunction "E_E") (pintype "bidirectional"))
      (node (ref "T16") (pin "E") (pinfunction "E_E") (pintype "bidirectional"))
      (node (ref "T2") (pin "E") (pinfunction "E_E") (pintype "bidirectional"))
      (node (ref "T3") (pin "E") (pinfunction "E_E") (pintype "bidirectional"))
      (node (ref "T4") (pin "E") (pinfunction "E_E") (pintype "bidirectional"))
      (node (ref "T5") (pin "E") (pinfunction "E_E") (pintype "bidirectional"))
      (node (ref "T6") (pin "E") (pinfunction "E_E") (pintype "bidirectional"))
      (node (ref "T7") (pin "E") (pinfunction "E_E") (pintype "bidirectional"))
      (node (ref "T8") (pin "E") (pinfunction "E_E") (pintype "bidirectional"))
      (node (ref "T9") (pin "E") (pinfunction "E_E") (pintype "bidirectional"))
    )
    (net (code "19") (name "GO") (class "Default")
      (node (ref "IC1") (pin "61") (pinfunction "PD14_61") (pintype "bidirectional"))
      (node (ref "START") (pin "1") (pinfunction "1_1") (pintype "passive"))
    )
    (net (code "20") (name "JETSON_RX") (class "Default")
      (node (ref "IC1") (pin "64") (pinfunction "PC7_64") (pintype "bidirectional"))
      (node (ref "JETSON") (pin "3") (pinfunction "3_3") (pintype "passive"))
    )
    (net (code "21") (name "JETSON_TX") (class "Default")
      (node (ref "IC1") (pin "63") (pinfunction "PC6_63") (pintype "bidirectional"))
      (node (ref "JETSON") (pin "2") (pinfunction "2_2") (pintype "passive"))
    )
    (net (code "22") (name "KICKER_RX") (class "Default")
      (node (ref "IC1") (pin "83") (pinfunction "PD2_83") (pintype "bidirectional"))
      (node (ref "KICKER") (pin "3") (pinfunction "3_3") (pintype "passive"))
    )
    (net (code "23") (name "KICKER_TX") (class "Default")
      (node (ref "IC1") (pin "80") (pinfunction "PC12_80") (pintype "bidirectional"))
      (node (ref "KICKER") (pin "1") (pinfunction "1_1") (pintype "passive"))
    )
    (net (code "24") (name "LED0") (class "Default")
      (node (ref "IC1") (pin "57") (pinfunction "PD10_57") (pintype "bidirectional"))
      (node (ref "LED20") (pin "A") (pinfunction "A_A") (pintype "passive"))
    )
    (net (code "25") (name "LED1") (class "Default")
      (node (ref "IC1") (pin "58") (pinfunction "PD11_58") (pintype "bidirectional"))
      (node (ref "LED17") (pin "A") (pinfunction "A_A") (pintype "passive"))
    )
    (net (code "26") (name "LED2") (class "Default")
      (node (ref "IC1") (pin "59") (pinfunction "PD12_59") (pintype "bidirectional"))
      (node (ref "LED18") (pin "A") (pinfunction "A_A") (pintype "passive"))
    )
    (net (code "27") (name "LED3") (class "Default")
      (node (ref "IC1") (pin "60") (pinfunction "PD13_60") (pintype "bidirectional"))
      (node (ref "LED19") (pin "A") (pinfunction "A_A") (pintype "passive"))
    )
    (net (code "28") (name "M1_OUT1") (class "Default")
      (node (ref "DRIVER1") (pin "11") (pinfunction "11_11") (pintype "passive"))
      (node (ref "DRIVER1") (pin "12") (pinfunction "12_12") (pintype "passive"))
      (node (ref "DRIVER1") (pin "13") (pinfunction "13_13") (pintype "passive"))
      (node (ref "DRIVER1") (pin "14") (pinfunction "14_14") (pintype "passive"))
      (node (ref "MOTOR1") (pin "IN1") (pinfunction "IN1_IN1") (pintype "bidirectional"))
    )
    (net (code "29") (name "M1_OUT2") (class "Default")
      (node (ref "DRIVER1") (pin "10") (pinfunction "10_10") (pintype "passive"))
      (node (ref "DRIVER1") (pin "7") (pinfunction "7_7") (pintype "passive"))
      (node (ref "DRIVER1") (pin "8") (pinfunction "8_8") (pintype "passive"))
      (node (ref "DRIVER1") (pin "9") (pinfunction "9_9") (pintype "passive"))
      (node (ref "MOTOR1") (pin "IN2") (pinfunction "IN2_IN2") (pintype "bidirectional"))
    )
    (net (code "30") (name "M2_OUT1") (class "Default")
      (node (ref "DRIVER2") (pin "11") (pinfunction "11_11") (pintype "passive"))
      (node (ref "DRIVER2") (pin "12") (pinfunction "12_12") (pintype "passive"))
      (node (ref "DRIVER2") (pin "13") (pinfunction "13_13") (pintype "passive"))
      (node (ref "DRIVER2") (pin "14") (pinfunction "14_14") (pintype "passive"))
      (node (ref "MOTOR2") (pin "IN1") (pinfunction "IN1_IN1") (pintype "bidirectional"))
    )
    (net (code "31") (name "M2_OUT2") (class "Default")
      (node (ref "DRIVER2") (pin "10") (pinfunction "10_10") (pintype "passive"))
      (node (ref "DRIVER2") (pin "7") (pinfunction "7_7") (pintype "passive"))
      (node (ref "DRIVER2") (pin "8") (pinfunction "8_8") (pintype "passive"))
      (node (ref "DRIVER2") (pin "9") (pinfunction "9_9") (pintype "passive"))
      (node (ref "MOTOR2") (pin "IN2") (pinfunction "IN2_IN2") (pintype "bidirectional"))
    )
    (net (code "32") (name "M3_OUT1") (class "Default")
      (node (ref "DRIVER\\3") (pin "11") (pinfunction "11_11") (pintype "passive"))
      (node (ref "DRIVER\\3") (pin "12") (pinfunction "12_12") (pintype "passive"))
      (node (ref "DRIVER\\3") (pin "13") (pinfunction "13_13") (pintype "passive"))
      (node (ref "DRIVER\\3") (pin "14") (pinfunction "14_14") (pintype "passive"))
      (node (ref "MOTOR3") (pin "IN1") (pinfunction "IN1_IN1") (pintype "bidirectional"))
    )
    (net (code "33") (name "M3_OUT2") (class "Default")
      (node (ref "DRIVER\\3") (pin "10") (pinfunction "10_10") (pintype "passive"))
      (node (ref "DRIVER\\3") (pin "7") (pinfunction "7_7") (pintype "passive"))
      (node (ref "DRIVER\\3") (pin "8") (pinfunction "8_8") (pintype "passive"))
      (node (ref "DRIVER\\3") (pin "9") (pinfunction "9_9") (pintype "passive"))
      (node (ref "MOTOR3") (pin "IN2") (pinfunction "IN2_IN2") (pintype "bidirectional"))
    )
    (net (code "34") (name "M4_OUT1") (class "Default")
      (node (ref "DRIVER4") (pin "11") (pinfunction "11_11") (pintype "passive"))
      (node (ref "DRIVER4") (pin "12") (pinfunction "12_12") (pintype "passive"))
      (node (ref "DRIVER4") (pin "13") (pinfunction "13_13") (pintype "passive"))
      (node (ref "DRIVER4") (pin "14") (pinfunction "14_14") (pintype "passive"))
      (node (ref "MOTOR4") (pin "IN1") (pinfunction "IN1_IN1") (pintype "bidirectional"))
    )
    (net (code "35") (name "M4_OUT2") (class "Default")
      (node (ref "DRIVER4") (pin "10") (pinfunction "10_10") (pintype "passive"))
      (node (ref "DRIVER4") (pin "7") (pinfunction "7_7") (pintype "passive"))
      (node (ref "DRIVER4") (pin "8") (pinfunction "8_8") (pintype "passive"))
      (node (ref "DRIVER4") (pin "9") (pinfunction "9_9") (pintype "passive"))
      (node (ref "MOTOR4") (pin "IN2") (pinfunction "IN2_IN2") (pintype "bidirectional"))
    )
    (net (code "36") (name "MOTOR_RX") (class "Default")
      (node (ref "DRIVER4") (pin "2") (pinfunction "2_2") (pintype "passive"))
      (node (ref "IC1") (pin "87") (pinfunction "PD6_87") (pintype "bidirectional"))
    )
    (net (code "37") (name "MOTOR_TX") (class "Default")
      (node (ref "DRIVER1") (pin "4") (pinfunction "4_4") (pintype "passive"))
      (node (ref "IC1") (pin "86") (pinfunction "PD5_86") (pintype "bidirectional"))
    )
    (net (code "38") (name "Net-(BATTERY-PadIN1)") (class "Default")
      (node (ref "BATTERY") (pin "IN1") (pinfunction "IN1_IN1") (pintype "bidirectional"))
      (node (ref "KEY") (pin "IN2") (pinfunction "IN2_IN2") (pintype "bidirectional"))
    )
    (net (code "39") (name "Net-(IC1A-VDDA)") (class "Default")
      (node (ref "C12") (pin "1") (pinfunction "1_1") (pintype "passive"))
      (node (ref "IC1") (pin "21") (pinfunction "VREF+_21") (pintype "input"))
      (node (ref "IC1") (pin "22") (pinfunction "VDDA_22") (pintype "power_in"))
      (node (ref "R33") (pin "1") (pinfunction "1_1") (pintype "passive"))
    )
    (net (code "40") (name "Net-(IC1M-VCAP1)") (class "Default")
      (node (ref "C7") (pin "2") (pinfunction "2_2") (pintype "passive"))
      (node (ref "IC1") (pin "49") (pinfunction "VCAP1_49") (pintype "power_in"))
    )
    (net (code "41") (name "Net-(IC1M-VCAP2)") (class "Default")
      (node (ref "C8") (pin "2") (pinfunction "2_2") (pintype "passive"))
      (node (ref "IC1") (pin "73") (pinfunction "VCAP2_73") (pintype "power_in"))
    )
    (net (code "42") (name "Net-(IC1N-BOOT0)") (class "Default")
      (node (ref "IC1") (pin "94") (pinfunction "BOOT0_94") (pintype "input"))
      (node (ref "R34") (pin "2") (pinfunction "2_2") (pintype "passive"))
      (node (ref "SJ1") (pin "1") (pinfunction "1_1") (pintype "passive"))
    )
    (net (code "43") (name "Net-(LED1-PadA)") (class "Default")
      (node (ref "LED1") (pin "A") (pinfunction "A_A") (pintype "passive"))
      (node (ref "R1") (pin "1") (pinfunction "1_1") (pintype "passive"))
    )
    (net (code "44") (name "Net-(LED1-PadC)") (class "Default")
      (node (ref "LED1") (pin "C") (pinfunction "C_C") (pintype "passive"))
      (node (ref "LED10") (pin "C") (pinfunction "C_C") (pintype "passive"))
      (node (ref "LED11") (pin "C") (pinfunction "C_C") (pintype "passive"))
      (node (ref "LED12") (pin "C") (pinfunction "C_C") (pintype "passive"))
      (node (ref "LED13") (pin "C") (pinfunction "C_C") (pintype "passive"))
      (node (ref "LED14") (pin "C") (pinfunction "C_C") (pintype "passive"))
      (node (ref "LED15") (pin "C") (pinfunction "C_C") (pintype "passive"))
      (node (ref "LED16") (pin "C") (pinfunction "C_C") (pintype "passive"))
      (node (ref "LED2") (pin "C") (pinfunction "C_C") (pintype "passive"))
      (node (ref "LED3") (pin "C") (pinfunction "C_C") (pintype "passive"))
      (node (ref "LED4") (pin "C") (pinfunction "C_C") (pintype "passive"))
      (node (ref "LED5") (pin "C") (pinfunction "C_C") (pintype "passive"))
      (node (ref "LED6") (pin "C") (pinfunction "C_C") (pintype "passive"))
      (node (ref "LED7") (pin "C") (pinfunction "C_C") (pintype "passive"))
      (node (ref "LED8") (pin "C") (pinfunction "C_C") (pintype "passive"))
      (node (ref "LED9") (pin "C") (pinfunction "C_C") (pintype "passive"))
      (node (ref "SJ2") (pin "2") (pinfunction "2_2") (pintype "passive"))
    )
    (net (code "45") (name "Net-(LED2-PadA)") (class "Default")
      (node (ref "LED2") (pin "A") (pinfunction "A_A") (pintype "passive"))
      (node (ref "R2") (pin "1") (pinfunction "1_1") (pintype "passive"))
    )
    (net (code "46") (name "Net-(LED3-PadA)") (class "Default")
      (node (ref "LED3") (pin "A") (pinfunction "A_A") (pintype "passive"))
      (node (ref "R3") (pin "1") (pinfunction "1_1") (pintype "passive"))
    )
    (net (code "47") (name "Net-(LED4-PadA)") (class "Default")
      (node (ref "LED4") (pin "A") (pinfunction "A_A") (pintype "passive"))
      (node (ref "R4") (pin "1") (pinfunction "1_1") (pintype "passive"))
    )
    (net (code "48") (name "Net-(LED5-PadA)") (class "Default")
      (node (ref "LED5") (pin "A") (pinfunction "A_A") (pintype "passive"))
      (node (ref "R5") (pin "1") (pinfunction "1_1") (pintype "passive"))
    )
    (net (code "49") (name "Net-(LED6-PadA)") (class "Default")
      (node (ref "LED6") (pin "A") (pinfunction "A_A") (pintype "passive"))
      (node (ref "R6") (pin "1") (pinfunction "1_1") (pintype "passive"))
    )
    (net (code "50") (name "Net-(LED7-PadA)") (class "Default")
      (node (ref "LED7") (pin "A") (pinfunction "A_A") (pintype "passive"))
      (node (ref "R7") (pin "1") (pinfunction "1_1") (pintype "passive"))
    )
    (net (code "51") (name "Net-(LED8-PadA)") (class "Default")
      (node (ref "LED8") (pin "A") (pinfunction "A_A") (pintype "passive"))
      (node (ref "R8") (pin "1") (pinfunction "1_1") (pintype "passive"))
    )
    (net (code "52") (name "Net-(LED9-PadA)") (class "Default")
      (node (ref "LED9") (pin "A") (pinfunction "A_A") (pintype "passive"))
      (node (ref "R9") (pin "1") (pinfunction "1_1") (pintype "passive"))
    )
    (net (code "53") (name "Net-(LED10-PadA)") (class "Default")
      (node (ref "LED10") (pin "A") (pinfunction "A_A") (pintype "passive"))
      (node (ref "R10") (pin "1") (pinfunction "1_1") (pintype "passive"))
    )
    (net (code "54") (name "Net-(LED11-PadA)") (class "Default")
      (node (ref "LED11") (pin "A") (pinfunction "A_A") (pintype "passive"))
      (node (ref "R11") (pin "1") (pinfunction "1_1") (pintype "passive"))
    )
    (net (code "55") (name "Net-(LED12-PadA)") (class "Default")
      (node (ref "LED12") (pin "A") (pinfunction "A_A") (pintype "passive"))
      (node (ref "R12") (pin "1") (pinfunction "1_1") (pintype "passive"))
    )
    (net (code "56") (name "Net-(LED13-PadA)") (class "Default")
      (node (ref "LED13") (pin "A") (pinfunction "A_A") (pintype "passive"))
      (node (ref "R13") (pin "1") (pinfunction "1_1") (pintype "passive"))
    )
    (net (code "57") (name "Net-(LED14-PadA)") (class "Default")
      (node (ref "LED14") (pin "A") (pinfunction "A_A") (pintype "passive"))
      (node (ref "R14") (pin "1") (pinfunction "1_1") (pintype "passive"))
    )
    (net (code "58") (name "Net-(LED15-PadA)") (class "Default")
      (node (ref "LED15") (pin "A") (pinfunction "A_A") (pintype "passive"))
      (node (ref "R15") (pin "1") (pinfunction "1_1") (pintype "passive"))
    )
    (net (code "59") (name "Net-(LED16-PadA)") (class "Default")
      (node (ref "LED16") (pin "A") (pinfunction "A_A") (pintype "passive"))
      (node (ref "R16") (pin "1") (pinfunction "1_1") (pintype "passive"))
    )
    (net (code "60") (name "Net-(LED17-PadC)") (class "Default")
      (node (ref "LED17") (pin "C") (pinfunction "C_C") (pintype "passive"))
      (node (ref "R36") (pin "2") (pinfunction "2_2") (pintype "passive"))
    )
    (net (code "61") (name "Net-(LED18-PadC)") (class "Default")
      (node (ref "LED18") (pin "C") (pinfunction "C_C") (pintype "passive"))
      (node (ref "R37") (pin "2") (pinfunction "2_2") (pintype "passive"))
    )
    (net (code "62") (name "Net-(LED19-PadC)") (class "Default")
      (node (ref "LED19") (pin "C") (pinfunction "C_C") (pintype "passive"))
      (node (ref "R38") (pin "2") (pinfunction "2_2") (pintype "passive"))
    )
    (net (code "63") (name "Net-(LED20-PadC)") (class "Default")
      (node (ref "LED20") (pin "C") (pinfunction "C_C") (pintype "passive"))
      (node (ref "R35") (pin "2") (pinfunction "2_2") (pintype "passive"))
    )
    (net (code "64") (name "Net-(R1-Pad2)") (class "Default")
      (node (ref "R1") (pin "2") (pinfunction "2_2") (pintype "passive"))
      (node (ref "R10") (pin "2") (pinfunction "2_2") (pintype "passive"))
      (node (ref "R11") (pin "2") (pinfunction "2_2") (pintype "passive"))
      (node (ref "R12") (pin "2") (pinfunction "2_2") (pintype "passive"))
      (node (ref "R13") (pin "2") (pinfunction "2_2") (pintype "passive"))
      (node (ref "R14") (pin "2") (pinfunction "2_2") (pintype "passive"))
      (node (ref "R15") (pin "2") (pinfunction "2_2") (pintype "passive"))
      (node (ref "R16") (pin "2") (pinfunction "2_2") (pintype "passive"))
      (node (ref "R2") (pin "2") (pinfunction "2_2") (pintype "passive"))
      (node (ref "R3") (pin "2") (pinfunction "2_2") (pintype "passive"))
      (node (ref "R4") (pin "2") (pinfunction "2_2") (pintype "passive"))
      (node (ref "R5") (pin "2") (pinfunction "2_2") (pintype "passive"))
      (node (ref "R6") (pin "2") (pinfunction "2_2") (pintype "passive"))
      (node (ref "R7") (pin "2") (pinfunction "2_2") (pintype "passive"))
      (node (ref "R8") (pin "2") (pinfunction "2_2") (pintype "passive"))
      (node (ref "R9") (pin "2") (pinfunction "2_2") (pintype "passive"))
      (node (ref "SJ3") (pin "1") (pinfunction "1_1") (pintype "passive"))
    )
    (net (code "65") (name "PS0") (class "Default")
      (node (ref "COMPASS_MODE") (pin "1") (pinfunction "1_1") (pintype "passive"))
      (node (ref "IC1") (pin "65") (pinfunction "PC8_65") (pintype "bidirectional"))
    )
    (net (code "66") (name "PS1") (class "Default")
      (node (ref "COMPASS_MODE") (pin "2") (pinfunction "2_2") (pintype "passive"))
      (node (ref "IC1") (pin "66") (pinfunction "PC9_66") (pintype "bidirectional"))
    )
    (net (code "67") (name "RST") (class "Default")
      (node (ref "IC1") (pin "14") (pinfunction "NRST_14") (pintype "bidirectional"))
      (node (ref "PROGRAMMER") (pin "1") (pinfunction "1_1") (pintype "passive"))
      (node (ref "RESET") (pin "1") (pinfunction "1_1") (pintype "passive"))
    )
    (net (code "68") (name "S1") (class "Default")
      (node (ref "IC1") (pin "36") (pinfunction "PB1_36") (pintype "bidirectional"))
      (node (ref "R17") (pin "1") (pinfunction "1_1") (pintype "passive"))
      (node (ref "T1") (pin "C") (pinfunction "C_C") (pintype "bidirectional"))
    )
    (net (code "69") (name "S2") (class "Default")
      (node (ref "IC1") (pin "35") (pinfunction "PB0_35") (pintype "bidirectional"))
      (node (ref "R18") (pin "1") (pinfunction "1_1") (pintype "passive"))
      (node (ref "T2") (pin "C") (pinfunction "C_C") (pintype "bidirectional"))
    )
    (net (code "70") (name "S3") (class "Default")
      (node (ref "IC1") (pin "34") (pinfunction "PC5_34") (pintype "bidirectional"))
      (node (ref "R19") (pin "1") (pinfunction "1_1") (pintype "passive"))
      (node (ref "T3") (pin "C") (pinfunction "C_C") (pintype "bidirectional"))
    )
    (net (code "71") (name "S4") (class "Default")
      (node (ref "IC1") (pin "33") (pinfunction "PC4_33") (pintype "bidirectional"))
      (node (ref "R20") (pin "1") (pinfunction "1_1") (pintype "passive"))
      (node (ref "T4") (pin "C") (pinfunction "C_C") (pintype "bidirectional"))
    )
    (net (code "72") (name "S5") (class "Default")
      (node (ref "IC1") (pin "32") (pinfunction "PA7_32") (pintype "bidirectional"))
      (node (ref "R21") (pin "1") (pinfunction "1_1") (pintype "passive"))
      (node (ref "T5") (pin "C") (pinfunction "C_C") (pintype "bidirectional"))
    )
    (net (code "73") (name "S6") (class "Default")
      (node (ref "IC1") (pin "31") (pinfunction "PA6_31") (pintype "bidirectional"))
      (node (ref "R22") (pin "1") (pinfunction "1_1") (pintype "passive"))
      (node (ref "T6") (pin "C") (pinfunction "C_C") (pintype "bidirectional"))
    )
    (net (code "74") (name "S7") (class "Default")
      (node (ref "IC1") (pin "30") (pinfunction "PA5_30") (pintype "bidirectional"))
      (node (ref "R23") (pin "1") (pinfunction "1_1") (pintype "passive"))
      (node (ref "T7") (pin "C") (pinfunction "C_C") (pintype "bidirectional"))
    )
    (net (code "75") (name "S8") (class "Default")
      (node (ref "IC1") (pin "29") (pinfunction "PA4_29") (pintype "bidirectional"))
      (node (ref "R24") (pin "1") (pinfunction "1_1") (pintype "passive"))
      (node (ref "T8") (pin "C") (pinfunction "C_C") (pintype "bidirectional"))
    )
    (net (code "76") (name "S9") (class "Default")
      (node (ref "IC1") (pin "26") (pinfunction "PA3_26") (pintype "bidirectional"))
      (node (ref "R25") (pin "1") (pinfunction "1_1") (pintype "passive"))
      (node (ref "T9") (pin "C") (pinfunction "C_C") (pintype "bidirectional"))
    )
    (net (code "77") (name "S10") (class "Default")
      (node (ref "IC1") (pin "25") (pinfunction "PA2_25") (pintype "bidirectional"))
      (node (ref "R26") (pin "1") (pinfunction "1_1") (pintype "passive"))
      (node (ref "T10") (pin "C") (pinfunction "C_C") (pintype "bidirectional"))
    )
    (net (code "78") (name "S11") (class "Default")
      (node (ref "IC1") (pin "24") (pinfunction "PA1_24") (pintype "bidirectional"))
      (node (ref "R27") (pin "1") (pinfunction "1_1") (pintype "passive"))
      (node (ref "T11") (pin "C") (pinfunction "C_C") (pintype "bidirectional"))
    )
    (net (code "79") (name "S12") (class "Default")
      (node (ref "IC1") (pin "23") (pinfunction "PA0_23") (pintype "bidirectional"))
      (node (ref "R28") (pin "1") (pinfunction "1_1") (pintype "passive"))
      (node (ref "T12") (pin "C") (pinfunction "C_C") (pintype "bidirectional"))
    )
    (net (code "80") (name "S13") (class "Default")
      (node (ref "IC1") (pin "18") (pinfunction "PC3_18") (pintype "bidirectional"))
      (node (ref "R29") (pin "1") (pinfunction "1_1") (pintype "passive"))
      (node (ref "T13") (pin "C") (pinfunction "C_C") (pintype "bidirectional"))
    )
    (net (code "81") (name "S14") (class "Default")
      (node (ref "IC1") (pin "17") (pinfunction "PC2_17") (pintype "bidirectional"))
      (node (ref "R30") (pin "1") (pinfunction "1_1") (pintype "passive"))
      (node (ref "T14") (pin "C") (pinfunction "C_C") (pintype "bidirectional"))
    )
    (net (code "82") (name "S15") (class "Default")
      (node (ref "IC1") (pin "16") (pinfunction "PC1_16") (pintype "bidirectional"))
      (node (ref "R31") (pin "1") (pinfunction "1_1") (pintype "passive"))
      (node (ref "T15") (pin "C") (pinfunction "C_C") (pintype "bidirectional"))
    )
    (net (code "83") (name "S16") (class "Default")
      (node (ref "IC1") (pin "15") (pinfunction "PC0_15") (pintype "bidirectional"))
      (node (ref "R32") (pin "1") (pinfunction "1_1") (pintype "passive"))
      (node (ref "T16") (pin "C") (pinfunction "C_C") (pintype "bidirectional"))
    )
    (net (code "84") (name "SYS_SWCLK") (class "Default")
      (node (ref "IC1") (pin "76") (pinfunction "PA14/SWCLK_76") (pintype "bidirectional"))
      (node (ref "PROGRAMMER") (pin "3") (pinfunction "3_3") (pintype "passive"))
    )
    (net (code "85") (name "SYS_SWDIO") (class "Default")
      (node (ref "IC1") (pin "72") (pinfunction "PA13/SWDIO_72") (pintype "bidirectional"))
      (node (ref "PROGRAMMER") (pin "2") (pinfunction "2_2") (pintype "passive"))
    )
    (net (code "86") (name "TEST_KICK") (class "Default")
      (node (ref "BUTTON") (pin "1") (pinfunction "1_1") (pintype "passive"))
      (node (ref "IC1") (pin "62") (pinfunction "PD15_62") (pintype "bidirectional"))
    )
    (net (code "87") (name "VCC") (class "Default")
      (node (ref "C11") (pin "2") (pinfunction "2_2") (pintype "passive"))
      (node (ref "C9") (pin "2") (pinfunction "2_2") (pintype "passive"))
      (node (ref "DEBUG_POWER") (pin "IN1") (pinfunction "IN1_IN1") (pintype "bidirectional"))
      (node (ref "DRIVER1") (pin "15") (pinfunction "15_15") (pintype "passive"))
      (node (ref "DRIVER1") (pin "16") (pinfunction "16_16") (pintype "passive"))
      (node (ref "DRIVER1") (pin "17") (pinfunction "17_17") (pintype "passive"))
      (node (ref "DRIVER2") (pin "15") (pinfunction "15_15") (pintype "passive"))
      (node (ref "DRIVER2") (pin "16") (pinfunction "16_16") (pintype "passive"))
      (node (ref "DRIVER2") (pin "17") (pinfunction "17_17") (pintype "passive"))
      (node (ref "DRIVER4") (pin "15") (pinfunction "15_15") (pintype "passive"))
      (node (ref "DRIVER4") (pin "16") (pinfunction "16_16") (pintype "passive"))
      (node (ref "DRIVER4") (pin "17") (pinfunction "17_17") (pintype "passive"))
      (node (ref "DRIVER\\3") (pin "15") (pinfunction "15_15") (pintype "passive"))
      (node (ref "DRIVER\\3") (pin "16") (pinfunction "16_16") (pintype "passive"))
      (node (ref "DRIVER\\3") (pin "17") (pinfunction "17_17") (pintype "passive"))
      (node (ref "IC2") (pin "1") (pinfunction "VI_1") (pintype "input"))
      (node (ref "IC3") (pin "1") (pinfunction "VI_1") (pintype "input"))
      (node (ref "KEY") (pin "IN1") (pinfunction "IN1_IN1") (pintype "bidirectional"))
      (node (ref "KICKER_POWER") (pin "IN1") (pinfunction "IN1_IN1") (pintype "bidirectional"))
    )
    (net (code "88") (name "unconnected-(COMPASS-Pad1)") (class "Default")
      (node (ref "COMPASS") (pin "1") (pinfunction "1_1") (pintype "passive"))
    )
    (net (code "89") (name "unconnected-(COMPASS-Pad5)") (class "Default")
      (node (ref "COMPASS") (pin "5") (pinfunction "5_5") (pintype "passive"))
    )
    (net (code "90") (name "unconnected-(DEBUG-Pad1)") (class "Default")
      (node (ref "DEBUG") (pin "1") (pinfunction "1_1") (pintype "passive"))
    )
    (net (code "91") (name "unconnected-(DEBUG-Pad4)") (class "Default")
      (node (ref "DEBUG") (pin "4") (pinfunction "4_4") (pintype "passive"))
    )
    (net (code "92") (name "unconnected-(DEBUG-Pad5)") (class "Default")
      (node (ref "DEBUG") (pin "5") (pinfunction "5_5") (pintype "passive"))
    )
    (net (code "93") (name "unconnected-(DRIVER1-Pad1)") (class "Default")
      (node (ref "DRIVER1") (pin "1") (pinfunction "1_1") (pintype "passive"))
    )
    (net (code "94") (name "unconnected-(DRIVER1-Pad3)") (class "Default")
      (node (ref "DRIVER1") (pin "3") (pinfunction "3_3") (pintype "passive"))
    )
    (net (code "95") (name "unconnected-(DRIVER1-Pad18)") (class "Default")
      (node (ref "DRIVER1") (pin "18") (pinfunction "18_18") (pintype "passive"))
    )
    (net (code "96") (name "unconnected-(DRIVER2-Pad1)") (class "Default")
      (node (ref "DRIVER2") (pin "1") (pinfunction "1_1") (pintype "passive"))
    )
    (net (code "97") (name "unconnected-(DRIVER2-Pad3)") (class "Default")
      (node (ref "DRIVER2") (pin "3") (pinfunction "3_3") (pintype "passive"))
    )
    (net (code "98") (name "unconnected-(DRIVER2-Pad18)") (class "Default")
      (node (ref "DRIVER2") (pin "18") (pinfunction "18_18") (pintype "passive"))
    )
    (net (code "99") (name "unconnected-(DRIVER4-Pad1)") (class "Default")
      (node (ref "DRIVER4") (pin "1") (pinfunction "1_1") (pintype "passive"))
    )
    (net (code "100") (name "unconnected-(DRIVER4-Pad3)") (class "Default")
      (node (ref "DRIVER4") (pin "3") (pinfunction "3_3") (pintype "passive"))
    )
    (net (code "101") (name "unconnected-(DRIVER4-Pad18)") (class "Default")
      (node (ref "DRIVER4") (pin "18") (pinfunction "18_18") (pintype "passive"))
    )
    (net (code "102") (name "unconnected-(DRIVER\\3-Pad1)") (class "Default")
      (node (ref "DRIVER\\3") (pin "1") (pinfunction "1_1") (pintype "passive"))
    )
    (net (code "103") (name "unconnected-(DRIVER\\3-Pad3)") (class "Default")
      (node (ref "DRIVER\\3") (pin "3") (pinfunction "3_3") (pintype "passive"))
    )
    (net (code "104") (name "unconnected-(DRIVER\\3-Pad18)") (class "Default")
      (node (ref "DRIVER\\3") (pin "18") (pinfunction "18_18") (pintype "passive"))
    )
    (net (code "105") (name "unconnected-(IC1B-PH0{slash}OSC_IN-Pad12)") (class "Default")
      (node (ref "IC1") (pin "12") (pinfunction "PH0/OSC_IN_12") (pintype "input"))
    )
    (net (code "106") (name "unconnected-(IC1B-PH1{slash}OSC_OUT-Pad13)") (class "Default")
      (node (ref "IC1") (pin "13") (pinfunction "PH1/OSC_OUT_13") (pintype "output"))
    )
    (net (code "107") (name "unconnected-(IC1C-PA8-Pad67)") (class "Default")
      (node (ref "IC1") (pin "67") (pinfunction "PA8_67") (pintype "bidirectional"))
    )
    (net (code "108") (name "unconnected-(IC1C-PA11-Pad70)") (class "Default")
      (node (ref "IC1") (pin "70") (pinfunction "PA11_70") (pintype "bidirectional"))
    )
    (net (code "109") (name "unconnected-(IC1C-PA12-Pad71)") (class "Default")
      (node (ref "IC1") (pin "71") (pinfunction "PA12_71") (pintype "bidirectional"))
    )
    (net (code "110") (name "unconnected-(IC1C-PA15-Pad77)") (class "Default")
      (node (ref "IC1") (pin "77") (pinfunction "PA15_77") (pintype "bidirectional"))
    )
    (net (code "111") (name "unconnected-(IC1E-PB8-Pad95)") (class "Default")
      (node (ref "IC1") (pin "95") (pinfunction "PB8_95") (pintype "bidirectional"))
    )
    (net (code "112") (name "unconnected-(IC1E-PB9-Pad96)") (class "Default")
      (node (ref "IC1") (pin "96") (pinfunction "PB9_96") (pintype "bidirectional"))
    )
    (net (code "113") (name "unconnected-(IC1F-PB2{slash}BOOT1-Pad37)") (class "Default")
      (node (ref "IC1") (pin "37") (pinfunction "PB2/BOOT1_37") (pintype "bidirectional"))
    )
    (net (code "114") (name "unconnected-(IC1F-PB3-Pad89)") (class "Default")
      (node (ref "IC1") (pin "89") (pinfunction "PB3_89") (pintype "bidirectional"))
    )
    (net (code "115") (name "unconnected-(IC1F-PB4-Pad90)") (class "Default")
      (node (ref "IC1") (pin "90") (pinfunction "PB4_90") (pintype "bidirectional"))
    )
    (net (code "116") (name "unconnected-(IC1F-PB5-Pad91)") (class "Default")
      (node (ref "IC1") (pin "91") (pinfunction "PB5_91") (pintype "bidirectional"))
    )
    (net (code "117") (name "unconnected-(IC1F-PB6-Pad92)") (class "Default")
      (node (ref "IC1") (pin "92") (pinfunction "PB6_92") (pintype "bidirectional"))
    )
    (net (code "118") (name "unconnected-(IC1F-PB7-Pad93)") (class "Default")
      (node (ref "IC1") (pin "93") (pinfunction "PB7_93") (pintype "bidirectional"))
    )
    (net (code "119") (name "unconnected-(IC1G-PC13-Pad7)") (class "Default")
      (node (ref "IC1") (pin "7") (pinfunction "PC13_7") (pintype "bidirectional"))
    )
    (net (code "120") (name "unconnected-(IC1G-PC14-Pad8)") (class "Default")
      (node (ref "IC1") (pin "8") (pinfunction "PC14_8") (pintype "bidirectional"))
    )
    (net (code "121") (name "unconnected-(IC1G-PC15-Pad9)") (class "Default")
      (node (ref "IC1") (pin "9") (pinfunction "PC15_9") (pintype "bidirectional"))
    )
    (net (code "122") (name "unconnected-(IC1J-PD0-Pad81)") (class "Default")
      (node (ref "IC1") (pin "81") (pinfunction "PD0_81") (pintype "bidirectional"))
    )
    (net (code "123") (name "unconnected-(IC1J-PD1-Pad82)") (class "Default")
      (node (ref "IC1") (pin "82") (pinfunction "PD1_82") (pintype "bidirectional"))
    )
    (net (code "124") (name "unconnected-(IC1J-PD3-Pad84)") (class "Default")
      (node (ref "IC1") (pin "84") (pinfunction "PD3_84") (pintype "bidirectional"))
    )
    (net (code "125") (name "unconnected-(IC1J-PD4-Pad85)") (class "Default")
      (node (ref "IC1") (pin "85") (pinfunction "PD4_85") (pintype "bidirectional"))
    )
    (net (code "126") (name "unconnected-(IC1J-PD7-Pad88)") (class "Default")
      (node (ref "IC1") (pin "88") (pinfunction "PD7_88") (pintype "bidirectional"))
    )
    (net (code "127") (name "unconnected-(IC1K-PE8-Pad39)") (class "Default")
      (node (ref "IC1") (pin "39") (pinfunction "PE8_39") (pintype "bidirectional"))
    )
    (net (code "128") (name "unconnected-(IC1K-PE9-Pad40)") (class "Default")
      (node (ref "IC1") (pin "40") (pinfunction "PE9_40") (pintype "bidirectional"))
    )
    (net (code "129") (name "unconnected-(IC1K-PE10-Pad41)") (class "Default")
      (node (ref "IC1") (pin "41") (pinfunction "PE10_41") (pintype "bidirectional"))
    )
    (net (code "130") (name "unconnected-(IC1K-PE11-Pad42)") (class "Default")
      (node (ref "IC1") (pin "42") (pinfunction "PE11_42") (pintype "bidirectional"))
    )
    (net (code "131") (name "unconnected-(IC1K-PE12-Pad43)") (class "Default")
      (node (ref "IC1") (pin "43") (pinfunction "PE12_43") (pintype "bidirectional"))
    )
    (net (code "132") (name "unconnected-(IC1K-PE13-Pad44)") (class "Default")
      (node (ref "IC1") (pin "44") (pinfunction "PE13_44") (pintype "bidirectional"))
    )
    (net (code "133") (name "unconnected-(IC1K-PE14-Pad45)") (class "Default")
      (node (ref "IC1") (pin "45") (pinfunction "PE14_45") (pintype "bidirectional"))
    )
    (net (code "134") (name "unconnected-(IC1K-PE15-Pad46)") (class "Default")
      (node (ref "IC1") (pin "46") (pinfunction "PE15_46") (pintype "bidirectional"))
    )
    (net (code "135") (name "unconnected-(IC1L-PE0-Pad97)") (class "Default")
      (node (ref "IC1") (pin "97") (pinfunction "PE0_97") (pintype "bidirectional"))
    )
    (net (code "136") (name "unconnected-(IC1L-PE1-Pad98)") (class "Default")
      (node (ref "IC1") (pin "98") (pinfunction "PE1_98") (pintype "bidirectional"))
    )
    (net (code "137") (name "unconnected-(IC1L-PE2-Pad1)") (class "Default")
      (node (ref "IC1") (pin "1") (pinfunction "PE2_1") (pintype "bidirectional"))
    )
    (net (code "138") (name "unconnected-(IC1L-PE3-Pad2)") (class "Default")
      (node (ref "IC1") (pin "2") (pinfunction "PE3_2") (pintype "bidirectional"))
    )
    (net (code "139") (name "unconnected-(IC1L-PE4-Pad3)") (class "Default")
      (node (ref "IC1") (pin "3") (pinfunction "PE4_3") (pintype "bidirectional"))
    )
    (net (code "140") (name "unconnected-(IC1L-PE5-Pad4)") (class "Default")
      (node (ref "IC1") (pin "4") (pinfunction "PE5_4") (pintype "bidirectional"))
    )
    (net (code "141") (name "unconnected-(IC1L-PE6-Pad5)") (class "Default")
      (node (ref "IC1") (pin "5") (pinfunction "PE6_5") (pintype "bidirectional"))
    )
    (net (code "142") (name "unconnected-(IC1L-PE7-Pad38)") (class "Default")
      (node (ref "IC1") (pin "38") (pinfunction "PE7_38") (pintype "bidirectional"))
    )
    (net (code "143") (name "unconnected-(JETSON-Pad1)") (class "Default")
      (node (ref "JETSON") (pin "1") (pinfunction "1_1") (pintype "passive"))
    )
    (net (code "144") (name "unconnected-(JETSON-Pad4)") (class "Default")
      (node (ref "JETSON") (pin "4") (pinfunction "4_4") (pintype "passive"))
    )
    (net (code "145") (name "unconnected-(JETSON-Pad5)") (class "Default")
      (node (ref "JETSON") (pin "5") (pinfunction "5_5") (pintype "passive"))
    )
  )
)
